# Sheet2.net
KiCad netlist of a schematic drawn in Altium Designer
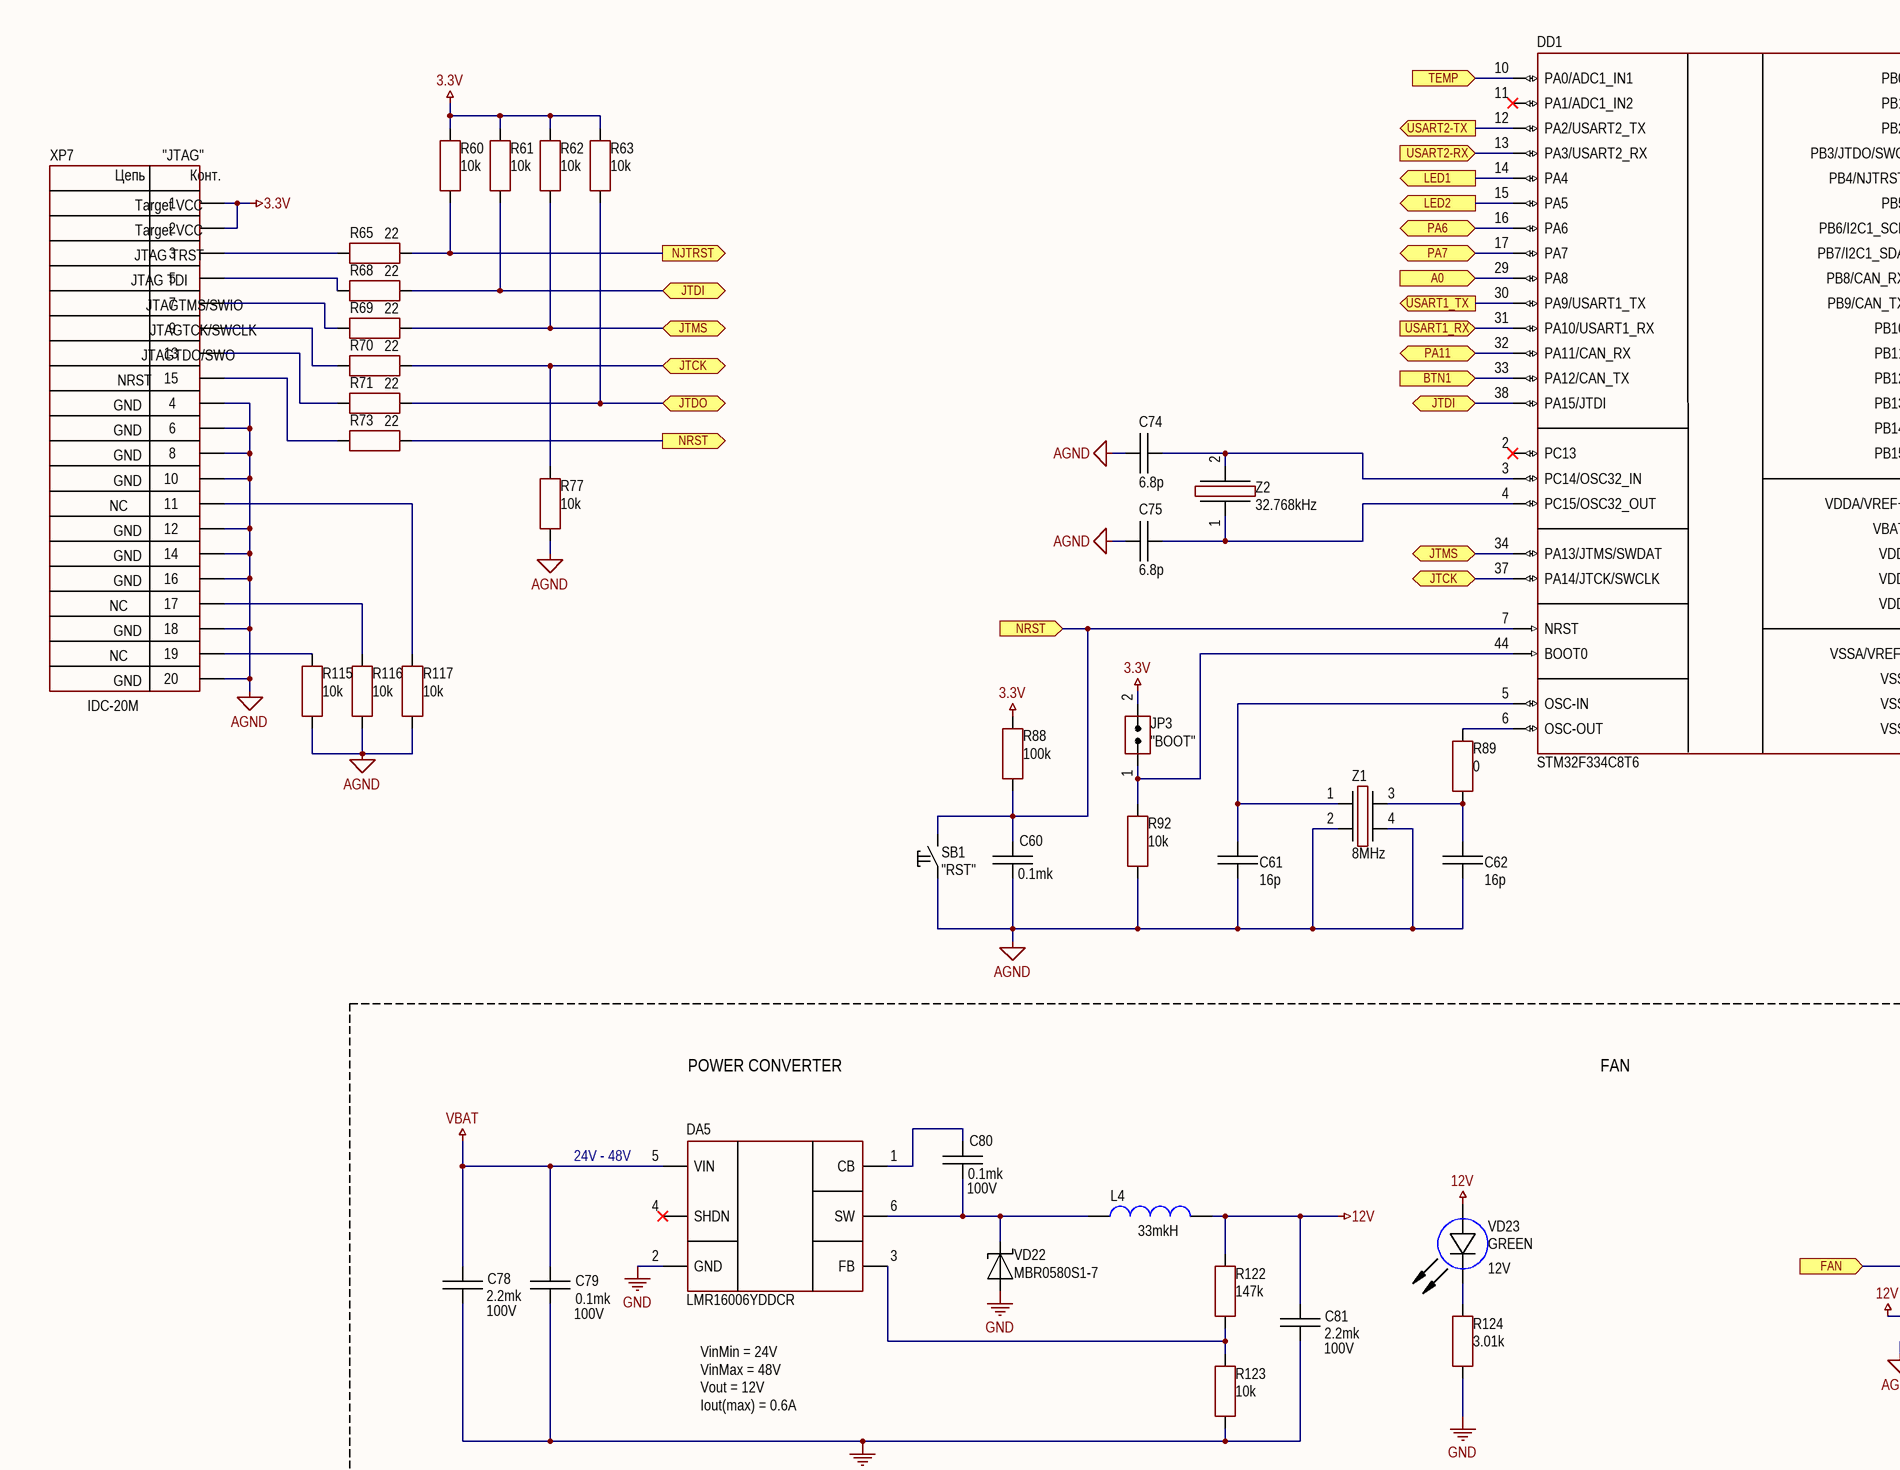
[diagram p0: Sheet2.SchDoc, top left]
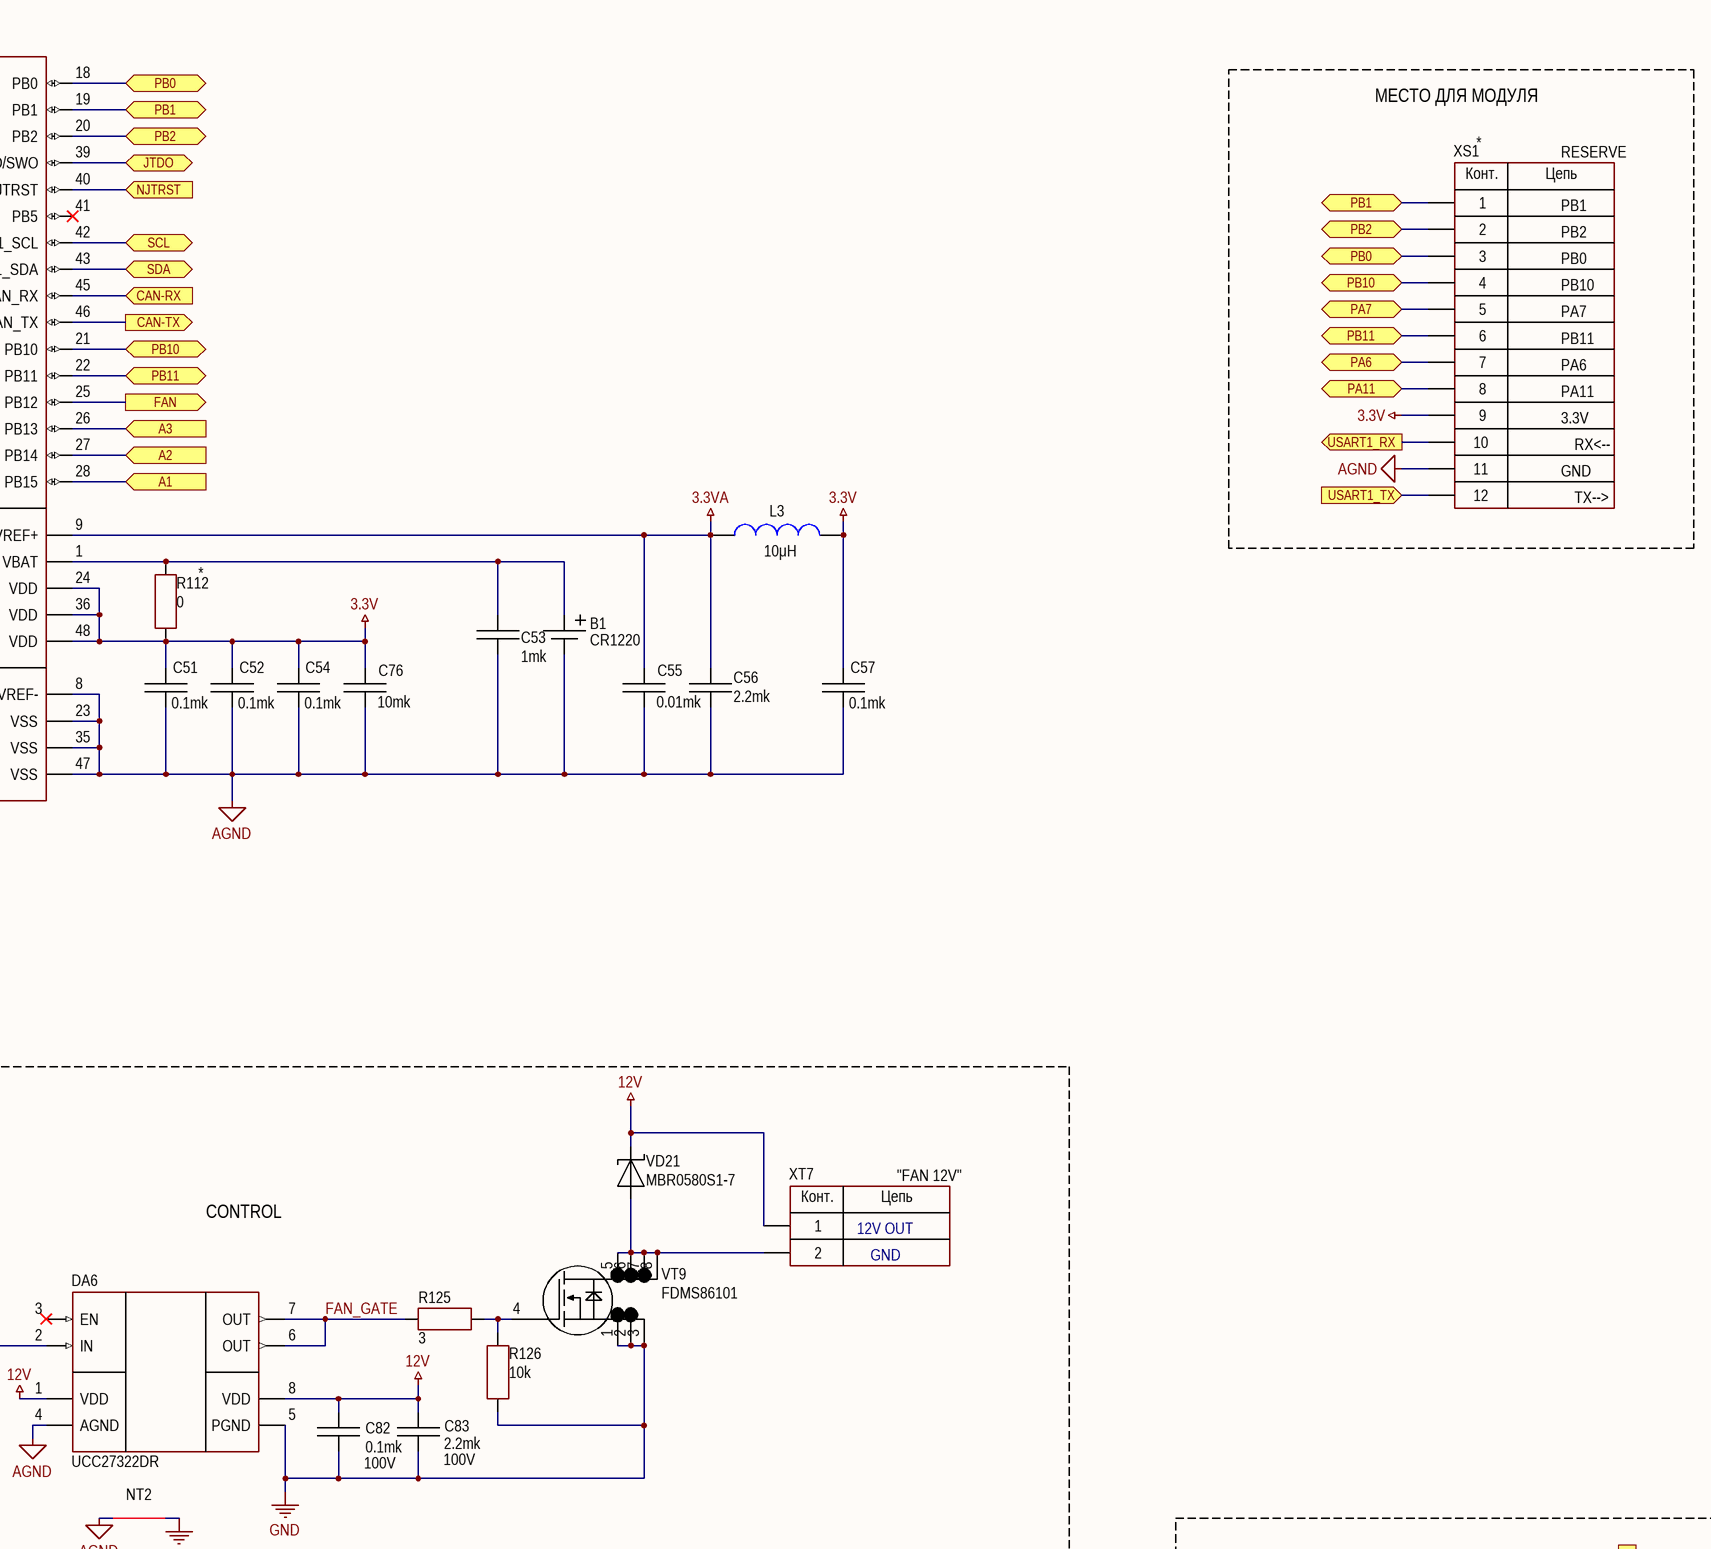
[diagram p1: Sheet2.SchDoc, top right]
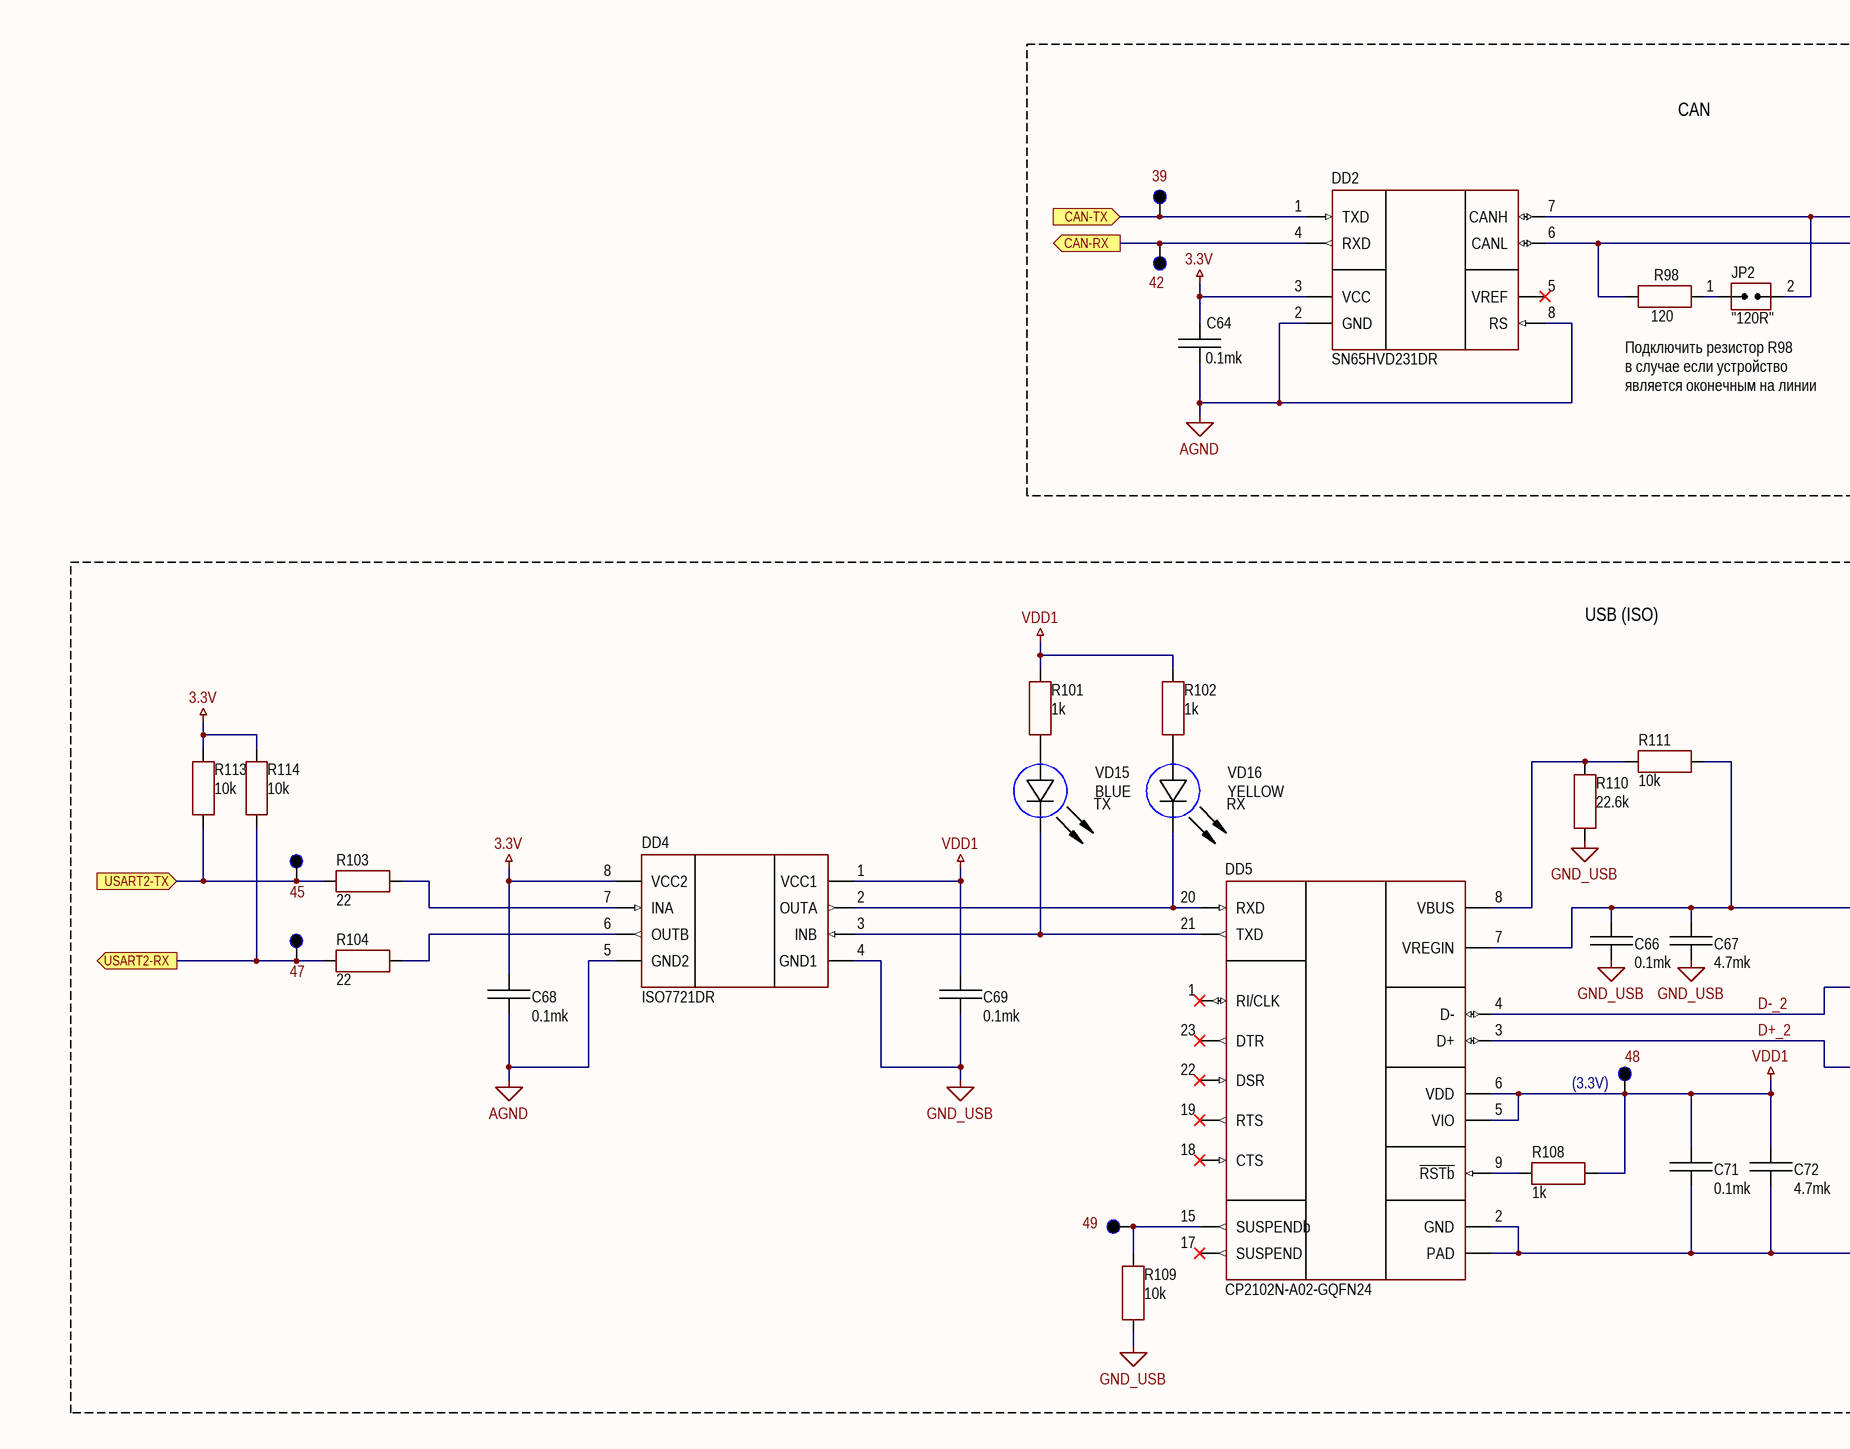
[diagram p2: Sheet2.SchDoc, bottom left]
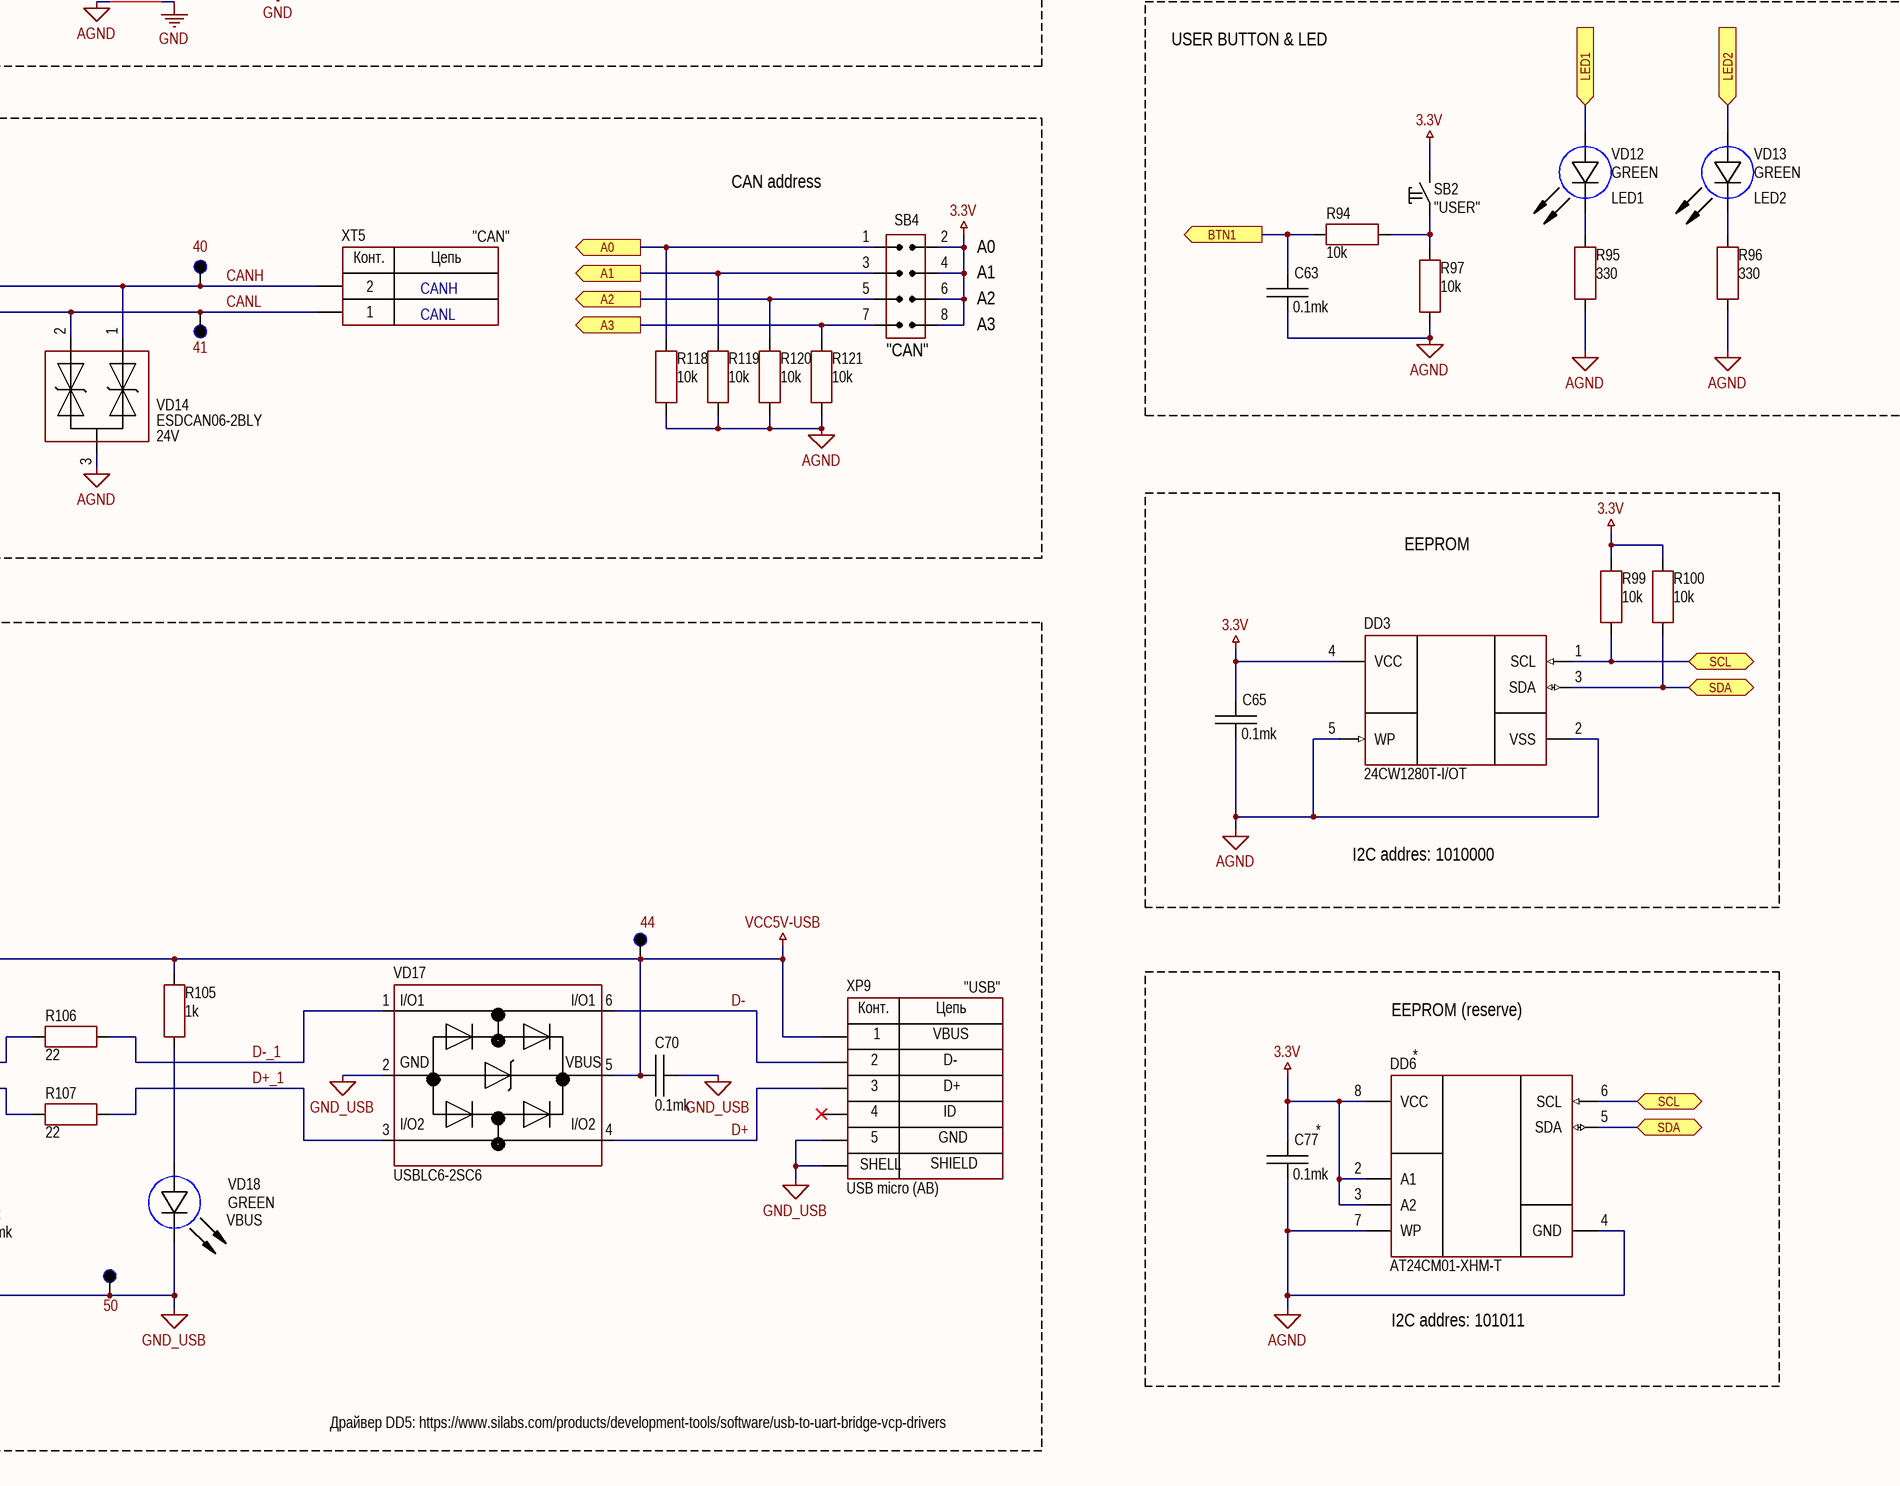
[diagram p3: Sheet2.SchDoc, bottom right]

(export (version "E")
  (design (tool "Eeschema 10.0.6"))
  (components
    (comp (ref "39")
      (value "test")
      (footprint "TEST_point_SMD")
      (description "Контактная площадка без компонента")
      (libsource (lib "Connector") (part "TEST point"))
    )
    (comp (ref "40")
      (value "test")
      (footprint "TEST_point_SMD")
      (description "Контактная площадка без компонента")
      (libsource (lib "Connector") (part "TEST point"))
    )
    (comp (ref "41")
      (value "test")
      (footprint "TEST_point_SMD")
      (description "Контактная площадка без компонента")
      (libsource (lib "Connector") (part "TEST point"))
    )
    (comp (ref "42")
      (value "test")
      (footprint "TEST_point_SMD")
      (description "Контактная площадка без компонента")
      (libsource (lib "Connector") (part "TEST point"))
    )
    (comp (ref "44")
      (value "test")
      (footprint "TEST_point_SMD")
      (description "Контактная площадка без компонента")
      (libsource (lib "Connector") (part "TEST point"))
    )
    (comp (ref "45")
      (value "test")
      (footprint "TEST_point_SMD")
      (description "Контактная площадка без компонента")
      (libsource (lib "Connector") (part "TEST point"))
    )
    (comp (ref "47")
      (value "test")
      (footprint "TEST_point_SMD")
      (description "Контактная площадка без компонента")
      (libsource (lib "Connector") (part "TEST point"))
    )
    (comp (ref "48")
      (value "test")
      (footprint "TEST_point_SMD")
      (description "Контактная площадка без компонента")
      (libsource (lib "Connector") (part "TEST point"))
    )
    (comp (ref "49")
      (value "test")
      (footprint "TEST_point_SMD")
      (description "Контактная площадка без компонента")
      (libsource (lib "Connector") (part "TEST point"))
    )
    (comp (ref "50")
      (value "test")
      (footprint "TEST_point_SMD")
      (description "Контактная площадка без компонента")
      (libsource (lib "Connector") (part "TEST point"))
    )
    (comp (ref "B1")
      (value "CR1220")
      (footprint "BAT: S8411-45R")
      (libsource (lib "Electromechanics") (part "CR1220"))
    )
    (comp (ref "C51")
      (value "0.1mk")
      (footprint "PCB_MPPT:CAP: 0603")
      (fields
        (field (name "MANUFACTURER") "AVX")
        (field (name "PARTNUMBER") "0603YC104KAT2A")
        (field (name "VALUEMANUFACTURERPARTNUMBER") "CAP CER, 0.1mk, X7R, ±10%, 16V, 0603")
      )
      (libsource (lib "Capacitor") (part "Ceramic_0603"))
    )
    (comp (ref "C52")
      (value "0.1mk")
      (footprint "PCB_MPPT:CAP: 0603")
      (fields
        (field (name "MANUFACTURER") "AVX")
        (field (name "PARTNUMBER") "0603YC104KAT2A")
        (field (name "VALUEMANUFACTURERPARTNUMBER") "CAP CER, 0.1mk, X7R, ±10%, 16V, 0603")
      )
      (libsource (lib "Capacitor") (part "Ceramic_0603"))
    )
    (comp (ref "C53")
      (value "1mk")
      (footprint "PCB_MPPT:CAP: 0603")
      (fields
        (field (name "MANUFACTURER") "AVX")
        (field (name "PARTNUMBER") "0603YC105KAT2A")
        (field (name "VALUEMANUFACTURERPARTNUMBER") "CAP CER, 1mk, X7R, ±10%, 16V, 0603")
      )
      (libsource (lib "Capacitor") (part "Ceramic_0603"))
    )
    (comp (ref "C54")
      (value "0.1mk")
      (footprint "PCB_MPPT:CAP: 0603")
      (fields
        (field (name "MANUFACTURER") "AVX")
        (field (name "PARTNUMBER") "0603YC104KAT2A")
        (field (name "VALUEMANUFACTURERPARTNUMBER") "CAP CER, 0.1mk, X7R, ±10%, 16V, 0603")
      )
      (libsource (lib "Capacitor") (part "Ceramic_0603"))
    )
    (comp (ref "C55")
      (value "0.01mk")
      (footprint "PCB_MPPT:CAP: 0603")
      (fields
        (field (name "MANUFACTURER") "AVX")
        (field (name "PARTNUMBER") "06031C103KAT2A")
        (field (name "VALUEMANUFACTURERPARTNUMBER") "CAP CER, 0.01mk, X7R, ±10%, 100V, 0603")
      )
      (libsource (lib "Capacitor") (part "Ceramic_0603"))
    )
    (comp (ref "C56")
      (value "2.2mk")
      (footprint "PCB_MPPT:CAP: 0603")
      (fields
        (field (name "MANUFACTURER") "AVX")
        (field (name "PARTNUMBER") "0603ZD225KAT2A")
        (field (name "VALUEMANUFACTURERPARTNUMBER") "CAP CER, 2.2mk, X5R, ±10%, 10V, 0603")
      )
      (libsource (lib "Capacitor") (part "Ceramic_0603"))
    )
    (comp (ref "C57")
      (value "0.1mk")
      (footprint "PCB_MPPT:CAP: 0603")
      (fields
        (field (name "MANUFACTURER") "AVX")
        (field (name "PARTNUMBER") "0603YC104KAT2A")
        (field (name "VALUEMANUFACTURERPARTNUMBER") "CAP CER, 0.1mk, X7R, ±10%, 16V, 0603")
      )
      (libsource (lib "Capacitor") (part "Ceramic_0603"))
    )
    (comp (ref "C60")
      (value "0.1mk")
      (footprint "PCB_MPPT:CAP: 0603")
      (fields
        (field (name "MANUFACTURER") "AVX")
        (field (name "PARTNUMBER") "0603YC104KAT2A")
        (field (name "VALUEMANUFACTURERPARTNUMBER") "CAP CER, 0.1mk, X7R, ±10%, 16V, 0603")
      )
      (libsource (lib "Capacitor") (part "Ceramic_0603"))
    )
    (comp (ref "C61")
      (value "16p")
      (footprint "PCB_MPPT:CAP: 0603")
      (fields
        (field (name "MANUFACTURER") "AVX")
        (field (name "PARTNUMBER") "06035A160JAT2A")
        (field (name "VALUEMANUFACTURERPARTNUMBER") "CAP CER, 16p, NP0, ±5%, 50V, 0603")
      )
      (libsource (lib "Capacitor") (part "Ceramic_0603"))
    )
    (comp (ref "C62")
      (value "16p")
      (footprint "PCB_MPPT:CAP: 0603")
      (fields
        (field (name "MANUFACTURER") "AVX")
        (field (name "PARTNUMBER") "06035A160JAT2A")
        (field (name "VALUEMANUFACTURERPARTNUMBER") "CAP CER, 16p, NP0, ±5%, 50V, 0603")
      )
      (libsource (lib "Capacitor") (part "Ceramic_0603"))
    )
    (comp (ref "C63")
      (value "0.1mk")
      (footprint "PCB_MPPT:CAP: 0603")
      (fields
        (field (name "MANUFACTURER") "AVX")
        (field (name "PARTNUMBER") "0603YC104KAT2A")
        (field (name "VALUEMANUFACTURERPARTNUMBER") "CAP CER, 0.1mk, X7R, ±10%, 16V, 0603")
      )
      (libsource (lib "Capacitor") (part "Ceramic_0603"))
    )
    (comp (ref "C64")
      (value "0.1mk")
      (footprint "PCB_MPPT:CAP: 0603")
      (fields
        (field (name "MANUFACTURER") "AVX")
        (field (name "PARTNUMBER") "0603YC104KAT2A")
        (field (name "VALUEMANUFACTURERPARTNUMBER") "CAP CER, 0.1mk, X7R, ±10%, 16V, 0603")
      )
      (libsource (lib "Capacitor") (part "Ceramic_0603"))
    )
    (comp (ref "C65")
      (value "0.1mk")
      (footprint "PCB_MPPT:CAP: 0603")
      (fields
        (field (name "MANUFACTURER") "AVX")
        (field (name "PARTNUMBER") "0603YC104KAT2A")
        (field (name "VALUEMANUFACTURERPARTNUMBER") "CAP CER, 0.1mk, X7R, ±10%, 16V, 0603")
      )
      (libsource (lib "Capacitor") (part "Ceramic_0603"))
    )
    (comp (ref "C66")
      (value "0.1mk")
      (footprint "PCB_MPPT:CAP: 0603")
      (fields
        (field (name "MANUFACTURER") "AVX")
        (field (name "PARTNUMBER") "0603YC104KAT2A")
        (field (name "VALUEMANUFACTURERPARTNUMBER") "CAP CER, 0.1mk, X7R, ±10%, 16V, 0603")
      )
      (libsource (lib "Capacitor") (part "Ceramic_0603"))
    )
    (comp (ref "C67")
      (value "4.7mk")
      (footprint "PCB_MPPT:CAP: 0805")
      (fields
        (field (name "MANUFACTURER") "AVX")
        (field (name "PARTNUMBER") "0805YC475KAT2A")
        (field (name "VALUEMANUFACTURERPARTNUMBER") "CAP CER, 4.7mk, X7R, ±10%, 16V, 0805")
      )
      (libsource (lib "Capacitor") (part "Ceramic_0805"))
    )
    (comp (ref "C68")
      (value "0.1mk")
      (footprint "PCB_MPPT:CAP: 0603")
      (fields
        (field (name "MANUFACTURER") "AVX")
        (field (name "PARTNUMBER") "0603YC104KAT2A")
        (field (name "VALUEMANUFACTURERPARTNUMBER") "CAP CER, 0.1mk, X7R, ±10%, 16V, 0603")
      )
      (libsource (lib "Capacitor") (part "Ceramic_0603"))
    )
    (comp (ref "C69")
      (value "0.1mk")
      (footprint "PCB_MPPT:CAP: 0603")
      (fields
        (field (name "MANUFACTURER") "AVX")
        (field (name "PARTNUMBER") "0603YC104KAT2A")
        (field (name "VALUEMANUFACTURERPARTNUMBER") "CAP CER, 0.1mk, X7R, ±10%, 16V, 0603")
      )
      (libsource (lib "Capacitor") (part "Ceramic_0603"))
    )
    (comp (ref "C70")
      (value "0.1mk")
      (footprint "PCB_MPPT:CAP: 0603")
      (fields
        (field (name "MANUFACTURER") "AVX")
        (field (name "PARTNUMBER") "0603YC104KAT2A")
        (field (name "VALUEMANUFACTURERPARTNUMBER") "CAP CER, 0.1mk, X7R, ±10%, 16V, 0603")
      )
      (libsource (lib "Capacitor") (part "Ceramic_0603"))
    )
    (comp (ref "C71")
      (value "0.1mk")
      (footprint "PCB_MPPT:CAP: 0603")
      (fields
        (field (name "MANUFACTURER") "AVX")
        (field (name "PARTNUMBER") "0603YC104KAT2A")
        (field (name "VALUEMANUFACTURERPARTNUMBER") "CAP CER, 0.1mk, X7R, ±10%, 16V, 0603")
      )
      (libsource (lib "Capacitor") (part "Ceramic_0603"))
    )
    (comp (ref "C72")
      (value "4.7mk")
      (footprint "PCB_MPPT:CAP: 0805")
      (fields
        (field (name "MANUFACTURER") "AVX")
        (field (name "PARTNUMBER") "0805YC475KAT2A")
        (field (name "VALUEMANUFACTURERPARTNUMBER") "CAP CER, 4.7mk, X7R, ±10%, 16V, 0805")
      )
      (libsource (lib "Capacitor") (part "Ceramic_0805"))
    )
    (comp (ref "C74")
      (value "6.8p")
      (footprint "PCB_MPPT:CAP: 0603")
      (fields
        (field (name "MANUFACTURER") "YAGEO")
        (field (name "PARTNUMBER") "CC0603DRNPO9BN6R8")
        (field (name "VALUEMANUFACTURERPARTNUMBER") "CAP CER, 6.8p, NP0, ±0.5pF, 50V, 0603")
      )
      (libsource (lib "Capacitor") (part "Ceramic_0603"))
    )
    (comp (ref "C75")
      (value "6.8p")
      (footprint "PCB_MPPT:CAP: 0603")
      (fields
        (field (name "MANUFACTURER") "YAGEO")
        (field (name "PARTNUMBER") "CC0603DRNPO9BN6R8")
        (field (name "VALUEMANUFACTURERPARTNUMBER") "CAP CER, 6.8p, NP0, ±0.5pF, 50V, 0603")
      )
      (libsource (lib "Capacitor") (part "Ceramic_0603"))
    )
    (comp (ref "C76")
      (value "10mk")
      (footprint "PCB_MPPT:CAP: 0603")
      (fields
        (field (name "MANUFACTURER") "AVX")
        (field (name "PARTNUMBER") "0603ZD106MAT2A")
        (field (name "VALUEMANUFACTURERPARTNUMBER") "CAP CER, 10mk, X5R, ±10%, 10V, 0603")
      )
      (libsource (lib "Capacitor") (part "Ceramic_0603"))
    )
    (comp (ref "C77")
      (value "0.1mk")
      (footprint "PCB_MPPT:CAP: 0603")
      (fields
        (field (name "MANUFACTURER") "AVX")
        (field (name "PARTNUMBER") "0603YC104KAT2A")
        (field (name "VALUEMANUFACTURERPARTNUMBER") "CAP CER, 0.1mk, X7R, ±10%, 16V, 0603")
      )
      (libsource (lib "Capacitor") (part "Ceramic_0603"))
    )
    (comp (ref "C78")
      (value "2.2mk")
      (footprint "PCB_MPPT:CAP: 1210")
      (fields
        (field (name "MANUFACTURER") "AVX")
        (field (name "PARTNUMBER") "12101C225KAT2A")
        (field (name "VALUEMANUFACTURERPARTNUMBER") "CAP CER, 2.2mk, X7R, ±10%, 100V, 1210")
        (field (name "VOLTAGE") "100V")
      )
      (libsource (lib "Capacitor") (part "Ceramic_1210"))
    )
    (comp (ref "C79")
      (value "0.1mk")
      (footprint "PCB_MPPT:CAP: 0603")
      (fields
        (field (name "MANUFACTURER") "AVX")
        (field (name "PARTNUMBER") "06031C104KAT2A")
        (field (name "VALUEMANUFACTURERPARTNUMBER") "CAP CER, 0.1mk, X7R, ±10%, 100V, 0603")
        (field (name "VOLTAGE") "100V")
      )
      (libsource (lib "Capacitor") (part "Ceramic_0603"))
    )
    (comp (ref "C80")
      (value "0.1mk")
      (footprint "PCB_MPPT:CAP: 0603")
      (fields
        (field (name "MANUFACTURER") "AVX")
        (field (name "PARTNUMBER") "06031C104KAT2A")
        (field (name "VALUEMANUFACTURERPARTNUMBER") "CAP CER, 0.1mk, X7R, ±10%, 100V, 0603")
        (field (name "VOLTAGE") "100V")
      )
      (libsource (lib "Capacitor") (part "Ceramic_0603"))
    )
    (comp (ref "C81")
      (value "2.2mk")
      (footprint "PCB_MPPT:CAP: 1210")
      (fields
        (field (name "MANUFACTURER") "AVX")
        (field (name "PARTNUMBER") "12101C225KAT2A")
        (field (name "VALUEMANUFACTURERPARTNUMBER") "CAP CER, 2.2mk, X7R, ±10%, 100V, 1210")
        (field (name "VOLTAGE") "100V")
      )
      (libsource (lib "Capacitor") (part "Ceramic_1210"))
    )
    (comp (ref "C82")
      (value "0.1mk")
      (footprint "PCB_MPPT:CAP: 0603")
      (fields
        (field (name "MANUFACTURER") "AVX")
        (field (name "PARTNUMBER") "06031C104KAT2A")
        (field (name "VALUEMANUFACTURERPARTNUMBER") "CAP CER, 0.1mk, X7R, ±10%, 100V, 0603")
        (field (name "VOLTAGE") "100V")
      )
      (libsource (lib "Capacitor") (part "Ceramic_0603"))
    )
    (comp (ref "C83")
      (value "2.2mk")
      (footprint "PCB_MPPT:CAP: 1210")
      (fields
        (field (name "MANUFACTURER") "AVX")
        (field (name "PARTNUMBER") "12101C225KAT2A")
        (field (name "VALUEMANUFACTURERPARTNUMBER") "CAP CER, 2.2mk, X7R, ±10%, 100V, 1210")
        (field (name "VOLTAGE") "100V")
      )
      (libsource (lib "Capacitor") (part "Ceramic_1210"))
    )
    (comp (ref "DA5")
      (value "~")
      (footprint "StandardCase:SOT23-6 Thin")
      (description "Buck converter")
      (fields
        (field (name "MANUFACTURER") "Texas Instruments")
        (field (name "VALUEMANUFACTURERPARTNUMBER") "DC/DC buck converter, SOT23-6")
        (field (name "PARTNUMBER") "LMR16006YDDCR")
      )
      (libsource (lib "IC. Power supply") (part "LMR16006YDDCR"))
    )
    (comp (ref "DA6")
      (value "~")
      (footprint "StandardCase:8-SOIC")
      (description "Gate driver")
      (fields
        (field (name "MANUFACTURER") "Texas Instruments")
        (field (name "VALUEMANUFACTURERPARTNUMBER") "Low side gate driver, P+N channel, 500kHz, ±9A, supply 4...15V, -40...+125°C, 8-SOIC")
        (field (name "PARTNUMBER") "UCC27322DR")
      )
      (libsource (lib "IC. Gate driver") (part "UCC27322D"))
    )
    (comp (ref "DD1")
      (value "IC microcontroller, 32-Bit, Cortex-M4, 72MHz, 64KB, 12KB, 48-LQFP")
      (footprint "PCB_MPPT:48-LQFP")
      (description "Cortex-M4")
      (fields (field (name "MANUFACTURER") "STMicroelectronics") (field (name "PARTNUMBER") "STM32F334C8T6"))
      (libsource (lib "IC. MCU") (part "STM32F334C4T6"))
    )
    (comp (ref "DD2")
      (value "~")
      (footprint "PCB_MPPT:8-SOIC")
      (description "CAN")
      (fields
        (field (name "MANUFACTURER") "Texas Instruments")
        (field (name "VALUEMANUFACTURERPARTNUMBER") "IC CAN transceiver, 8-SOIC")
        (field (name "PARTNUMBER") "SN65HVD231DR")
      )
      (libsource (lib "IC. Interface") (part "SN65HVD231DR"))
    )
    (comp (ref "DD3")
      (value "~")
      (footprint "PCB_MPPT:SOT23-5")
      (description "EEPROM")
      (fields
        (field (name "MANUFACTURER") "Microchip Technology")
        (field (name "VALUEMANUFACTURERPARTNUMBER") "EEPROM, 128KB (16Kx8), 400 kHz, I2C, SOT-23-5")
        (field (name "PARTNUMBER") "24CW1280T-I/OT")
      )
      (libsource (lib "IC. Memory") (part "24AA01T"))
    )
    (comp (ref "DD4")
      (value "~")
      (footprint "PCB_MPPT:8-SOIC")
      (description "Digital isolator")
      (fields
        (field (name "MANUFACTURER") "Texas Instruments")
        (field (name "VALUEMANUFACTURERPARTNUMBER") "IC digital isolator, 8-SOIC")
        (field (name "PARTNUMBER") "ISO7721DR")
      )
      (libsource (lib "IC. Interface") (part "ISO7721DR"))
    )
    (comp (ref "DD5")
      (value "~")
      (footprint "PCB_MPPT:24-QFN")
      (description "USB-to-UART")
      (fields
        (field (name "MANUFACTURER") "Silicon Labs")
        (field (name "VALUEMANUFACTURERPARTNUMBER") "USB Bridge, USB to UART, USB2.0, 24-QFN(4x4)")
        (field (name "PARTNUMBER") "CP2102N-A02-GQFN24")
      )
      (libsource (lib "IC. Interface") (part "CP2102N_QFN24"))
    )
    (comp (ref "DD6")
      (value "EEPROM Memory IC 1Mb (128K x 8) I²C 1MHz 550ns 8-TSSOP")
      (footprint "8-TSSOP")
      (description "EEPROM")
      (fields
        (field (name "MANUFACTURER") "Microchip Technology")
        (field (name "PARTNUMBER") "AT24CM01-XHM-T")
      )
      (libsource (lib "IC. Memory") (part "AT24CM01-XHM-T"))
    )
    (comp (ref "JP2")
      (value "~")
      (footprint "PCB_MPPT:CON: PLS-2")
      (fields
        (field (name "COMMENTTEXT") "\"120R\"")
        (field (name "MANUFACTURER") "Würth Elektronik")
        (field (name "PARTNUMBER") "61300411121")
        (field (name "VALUEMANUFACTURERPARTNUMBER") "PLS-2 SINGLE ROW, 2pin, 2.54mm, 500VAC, 3A")
      )
      (libsource (lib "") (part "Jumper_single_1"))
    )
    (comp (ref "JP3")
      (value "~")
      (footprint "PCB_MPPT:CON: PLS-2")
      (fields
        (field (name "COMMENTTEXT") "\"BOOT\"")
        (field (name "MANUFACTURER") "Würth Elektronik")
        (field (name "PARTNUMBER") "61300411121")
        (field (name "VALUEMANUFACTURERPARTNUMBER") "PLS-2 SINGLE ROW, 2pin, 2.54mm, 500VAC, 3A")
      )
      (libsource (lib "Connector") (part "Jumper_single"))
    )
    (comp (ref "L3")
      (value "10μH")
      (footprint "PCB_MPPT:IND: 0805")
      (fields
        (field (name "MANUFACTURER") "Murata Electronics")
        (field (name "PARTNUMBER") "LQM21DH100M70L")
        (field (name "VALUEMANUFACTURERPARTNUMBER") "Fixed inductor, 10μH, ±20%, 0805, 250mA")
      )
      (libsource (lib "Inductor") (part "Inductor_0805"))
    )
    (comp (ref "L4")
      (value "33mkH")
      (footprint "PCB_MPPT:IND: SRU8043")
      (fields
        (field (name "MANUFACTURER") "Bourns Inc.")
        (field (name "PARTNUMBER") "SRU8043-330Y")
        (field (name "VALUEMANUFACTURERPARTNUMBER") "Fixed inductor, 33mkH, ±15%, SMD Nonstandard, Ferrite, , 1.7A")
      )
      (libsource (lib "Inductor") (part "Inductor_R22.9/14/7.62"))
    )
    (comp (ref "NT2")
      (value "~")
      (footprint "PCB_MPPT:NET_TIE")
      (libsource (lib "Connector") (part "NetTie"))
    )
    (comp (ref "R60")
      (value "10k")
      (footprint "PCB_MPPT:RES: 0603")
      (fields
        (field (name "MANUFACTURER") "Vishay")
        (field (name "PARTNUMBER") "CRCW060310K0JNEAC")
        (field (name "VALUEMANUFACTURERPARTNUMBER") "Res, SMD, 10k, ±5%, 0603, 0.1W")
      )
      (libsource (lib "Resistor") (part "Resistor_0603"))
    )
    (comp (ref "R61")
      (value "10k")
      (footprint "PCB_MPPT:RES: 0603")
      (fields
        (field (name "MANUFACTURER") "Vishay")
        (field (name "PARTNUMBER") "CRCW060310K0JNEAC")
        (field (name "VALUEMANUFACTURERPARTNUMBER") "Res, SMD, 10k, ±5%, 0603, 0.1W")
      )
      (libsource (lib "Resistor") (part "Resistor_0603"))
    )
    (comp (ref "R62")
      (value "10k")
      (footprint "PCB_MPPT:RES: 0603")
      (fields
        (field (name "MANUFACTURER") "Vishay")
        (field (name "PARTNUMBER") "CRCW060310K0JNEAC")
        (field (name "VALUEMANUFACTURERPARTNUMBER") "Res, SMD, 10k, ±5%, 0603, 0.1W")
      )
      (libsource (lib "Resistor") (part "Resistor_0603"))
    )
    (comp (ref "R63")
      (value "10k")
      (footprint "PCB_MPPT:RES: 0603")
      (fields
        (field (name "MANUFACTURER") "Vishay")
        (field (name "PARTNUMBER") "CRCW060310K0JNEAC")
        (field (name "VALUEMANUFACTURERPARTNUMBER") "Res, SMD, 10k, ±5%, 0603, 0.1W")
      )
      (libsource (lib "Resistor") (part "Resistor_0603"))
    )
    (comp (ref "R65")
      (value "22")
      (footprint "PCB_MPPT:RES: 0603")
      (fields
        (field (name "MANUFACTURER") "Vishay")
        (field (name "PARTNUMBER") "CRCW060322R0JNEA")
        (field (name "VALUEMANUFACTURERPARTNUMBER") "Res, SMD, 22, ±5%, 0603, 0.1W")
      )
      (libsource (lib "") (part "Resistor_0603_1"))
    )
    (comp (ref "R68")
      (value "22")
      (footprint "PCB_MPPT:RES: 0603")
      (fields
        (field (name "MANUFACTURER") "Vishay")
        (field (name "PARTNUMBER") "CRCW060322R0JNEA")
        (field (name "VALUEMANUFACTURERPARTNUMBER") "Res, SMD, 22, ±5%, 0603, 0.1W")
      )
      (libsource (lib "") (part "Resistor_0603_1"))
    )
    (comp (ref "R69")
      (value "22")
      (footprint "PCB_MPPT:RES: 0603")
      (fields
        (field (name "MANUFACTURER") "Vishay")
        (field (name "PARTNUMBER") "CRCW060322R0JNEA")
        (field (name "VALUEMANUFACTURERPARTNUMBER") "Res, SMD, 22, ±5%, 0603, 0.1W")
      )
      (libsource (lib "") (part "Resistor_0603_1"))
    )
    (comp (ref "R70")
      (value "22")
      (footprint "PCB_MPPT:RES: 0603")
      (fields
        (field (name "MANUFACTURER") "Vishay")
        (field (name "PARTNUMBER") "CRCW060322R0JNEA")
        (field (name "VALUEMANUFACTURERPARTNUMBER") "Res, SMD, 22, ±5%, 0603, 0.1W")
      )
      (libsource (lib "") (part "Resistor_0603_1"))
    )
    (comp (ref "R71")
      (value "22")
      (footprint "PCB_MPPT:RES: 0603")
      (fields
        (field (name "MANUFACTURER") "Vishay")
        (field (name "PARTNUMBER") "CRCW060322R0JNEA")
        (field (name "VALUEMANUFACTURERPARTNUMBER") "Res, SMD, 22, ±5%, 0603, 0.1W")
      )
      (libsource (lib "") (part "Resistor_0603_1"))
    )
    (comp (ref "R73")
      (value "22")
      (footprint "PCB_MPPT:RES: 0603")
      (fields
        (field (name "MANUFACTURER") "Vishay")
        (field (name "PARTNUMBER") "CRCW060322R0JNEA")
        (field (name "VALUEMANUFACTURERPARTNUMBER") "Res, SMD, 22, ±5%, 0603, 0.1W")
      )
      (libsource (lib "") (part "Resistor_0603_1"))
    )
    (comp (ref "R77")
      (value "10k")
      (footprint "PCB_MPPT:RES: 0603")
      (fields
        (field (name "MANUFACTURER") "Vishay")
        (field (name "PARTNUMBER") "CRCW060310K0JNEAC")
        (field (name "VALUEMANUFACTURERPARTNUMBER") "Res, SMD, 10k, ±5%, 0603, 0.1W")
      )
      (libsource (lib "Resistor") (part "Resistor_0603"))
    )
    (comp (ref "R88")
      (value "100k")
      (footprint "PCB_MPPT:RES: 0603")
      (fields
        (field (name "MANUFACTURER") "Vishay")
        (field (name "PARTNUMBER") "CRCW0603100KFKEA")
        (field (name "VALUEMANUFACTURERPARTNUMBER") "Res, SMD, 100k, ±1%, 0603, 0.1W")
      )
      (libsource (lib "Resistor") (part "Resistor_0603"))
    )
    (comp (ref "R89")
      (value "0")
      (footprint "PCB_MPPT:RES: 0603")
      (fields
        (field (name "MANUFACTURER") "Vishay")
        (field (name "PARTNUMBER") "CRCW06030000Z0EA")
        (field (name "VALUEMANUFACTURERPARTNUMBER") "Res, SMD, 0, ±1%, 0603, 0.1W")
      )
      (libsource (lib "") (part "Resistor_0603_2"))
    )
    (comp (ref "R92")
      (value "10k")
      (footprint "PCB_MPPT:RES: 0603")
      (fields
        (field (name "MANUFACTURER") "Vishay")
        (field (name "PARTNUMBER") "CRCW060310K0JNEAC")
        (field (name "VALUEMANUFACTURERPARTNUMBER") "Res, SMD, 10k, ±5%, 0603, 0.1W")
      )
      (libsource (lib "Resistor") (part "Resistor_0603"))
    )
    (comp (ref "R94")
      (value "10k")
      (footprint "PCB_MPPT:RES: 0603")
      (fields
        (field (name "MANUFACTURER") "Vishay")
        (field (name "PARTNUMBER") "CRCW060310K0JNEAC")
        (field (name "VALUEMANUFACTURERPARTNUMBER") "Res, SMD, 10k, ±5%, 0603, 0.1W")
      )
      (libsource (lib "") (part "Resistor_0603_1"))
    )
    (comp (ref "R95")
      (value "330")
      (footprint "PCB_MPPT:RES: 0603")
      (fields
        (field (name "MANUFACTURER") "Vishay")
        (field (name "PARTNUMBER") "CRCW0603330RFKEAC")
        (field (name "VALUEMANUFACTURERPARTNUMBER") "Res, SMD, 330, ±1%, 0603, 0.1W")
      )
      (libsource (lib "Resistor") (part "Resistor_0603"))
    )
    (comp (ref "R96")
      (value "330")
      (footprint "PCB_MPPT:RES: 0603")
      (fields
        (field (name "MANUFACTURER") "Vishay")
        (field (name "PARTNUMBER") "CRCW0603330RFKEAC")
        (field (name "VALUEMANUFACTURERPARTNUMBER") "Res, SMD, 330, ±1%, 0603, 0.1W")
      )
      (libsource (lib "Resistor") (part "Resistor_0603"))
    )
    (comp (ref "R97")
      (value "10k")
      (footprint "PCB_MPPT:RES: 0603")
      (fields
        (field (name "MANUFACTURER") "Vishay")
        (field (name "PARTNUMBER") "CRCW060310K0JNEAC")
        (field (name "VALUEMANUFACTURERPARTNUMBER") "Res, SMD, 10k, ±5%, 0603, 0.1W")
      )
      (libsource (lib "Resistor") (part "Resistor_0603"))
    )
    (comp (ref "R98")
      (value "120")
      (footprint "PCB_MPPT:RES: 0805")
      (fields
        (field (name "MANUFACTURER") "Vishay")
        (field (name "PARTNUMBER") "CRCW0805120RJNEA")
        (field (name "VALUEMANUFACTURERPARTNUMBER") "Resistor film, 120, ±5%, 0805, 0.125W")
      )
      (libsource (lib "Resistor") (part "Resistor_0805"))
    )
    (comp (ref "R99")
      (value "10k")
      (footprint "PCB_MPPT:RES: 0603")
      (fields
        (field (name "MANUFACTURER") "Vishay")
        (field (name "PARTNUMBER") "CRCW060310K0JNEAC")
        (field (name "VALUEMANUFACTURERPARTNUMBER") "Res, SMD, 10k, ±5%, 0603, 0.1W")
      )
      (libsource (lib "") (part "Resistor_0603_2"))
    )
    (comp (ref "R100")
      (value "10k")
      (footprint "PCB_MPPT:RES: 0603")
      (fields
        (field (name "MANUFACTURER") "Vishay")
        (field (name "PARTNUMBER") "CRCW060310K0JNEAC")
        (field (name "VALUEMANUFACTURERPARTNUMBER") "Res, SMD, 10k, ±5%, 0603, 0.1W")
      )
      (libsource (lib "") (part "Resistor_0603_2"))
    )
    (comp (ref "R101")
      (value "1k")
      (footprint "PCB_MPPT:RES: 0603")
      (fields
        (field (name "MANUFACTURER") "Vishay")
        (field (name "PARTNUMBER") "CRCW06031K00FKEA")
        (field (name "VALUEMANUFACTURERPARTNUMBER") "Res, SMD, 1k, ±1%, 0603, 0.1W")
      )
      (libsource (lib "") (part "Resistor_0603_1"))
    )
    (comp (ref "R102")
      (value "1k")
      (footprint "PCB_MPPT:RES: 0603")
      (fields
        (field (name "MANUFACTURER") "Vishay")
        (field (name "PARTNUMBER") "CRCW06031K00FKEA")
        (field (name "VALUEMANUFACTURERPARTNUMBER") "Res, SMD, 1k, ±1%, 0603, 0.1W")
      )
      (libsource (lib "") (part "Resistor_0603_1"))
    )
    (comp (ref "R103")
      (value "22")
      (footprint "PCB_MPPT:RES: 0603")
      (fields
        (field (name "MANUFACTURER") "Vishay")
        (field (name "PARTNUMBER") "CRCW060322R0JNEA")
        (field (name "VALUEMANUFACTURERPARTNUMBER") "Res, SMD, 22, ±5%, 0603, 0.1W")
      )
      (libsource (lib "Resistor") (part "Resistor_0603"))
    )
    (comp (ref "R104")
      (value "22")
      (footprint "PCB_MPPT:RES: 0603")
      (fields
        (field (name "MANUFACTURER") "Vishay")
        (field (name "PARTNUMBER") "CRCW060322R0JNEA")
        (field (name "VALUEMANUFACTURERPARTNUMBER") "Res, SMD, 22, ±5%, 0603, 0.1W")
      )
      (libsource (lib "Resistor") (part "Resistor_0603"))
    )
    (comp (ref "R105")
      (value "1k")
      (footprint "PCB_MPPT:RES: 0603")
      (fields
        (field (name "MANUFACTURER") "Vishay")
        (field (name "PARTNUMBER") "CRCW06031K00FKEA")
        (field (name "VALUEMANUFACTURERPARTNUMBER") "Res, SMD, 1k, ±1%, 0603, 0.1W")
      )
      (libsource (lib "") (part "Resistor_0603_1"))
    )
    (comp (ref "R106")
      (value "22")
      (footprint "PCB_MPPT:RES: 0603")
      (fields
        (field (name "MANUFACTURER") "Vishay")
        (field (name "PARTNUMBER") "CRCW060322R0JNEA")
        (field (name "VALUEMANUFACTURERPARTNUMBER") "Res, SMD, 22, ±5%, 0603, 0.1W")
      )
      (libsource (lib "Resistor") (part "Resistor_0603"))
    )
    (comp (ref "R107")
      (value "22")
      (footprint "PCB_MPPT:RES: 0603")
      (fields
        (field (name "MANUFACTURER") "Vishay")
        (field (name "PARTNUMBER") "CRCW060322R0JNEA")
        (field (name "VALUEMANUFACTURERPARTNUMBER") "Res, SMD, 22, ±5%, 0603, 0.1W")
      )
      (libsource (lib "Resistor") (part "Resistor_0603"))
    )
    (comp (ref "R108")
      (value "1k")
      (footprint "PCB_MPPT:RES: 0603")
      (fields
        (field (name "MANUFACTURER") "Vishay")
        (field (name "PARTNUMBER") "CRCW06031K00FKEA")
        (field (name "VALUEMANUFACTURERPARTNUMBER") "Res, SMD, 1k, ±1%, 0603, 0.1W")
      )
      (libsource (lib "") (part "Resistor_0603_2"))
    )
    (comp (ref "R109")
      (value "10k")
      (footprint "PCB_MPPT:RES: 0603")
      (fields
        (field (name "MANUFACTURER") "Vishay")
        (field (name "PARTNUMBER") "CRCW060310K0JNEAC")
        (field (name "VALUEMANUFACTURERPARTNUMBER") "Res, SMD, 10k, ±5%, 0603, 0.1W")
      )
      (libsource (lib "Resistor") (part "Resistor_0603"))
    )
    (comp (ref "R110")
      (value "22.6k")
      (footprint "PCB_MPPT:RES: 0603")
      (fields
        (field (name "MANUFACTURER") "Vishay")
        (field (name "PARTNUMBER") "CRCW060322K6FKEA")
        (field (name "VALUEMANUFACTURERPARTNUMBER") "Res, SMD, 22.6k, ±1%, 0603, 0.1W")
      )
      (libsource (lib "") (part "Resistor_0603_2"))
    )
    (comp (ref "R111")
      (value "10k")
      (footprint "PCB_MPPT:RES: 0603")
      (fields
        (field (name "MANUFACTURER") "Vishay")
        (field (name "PARTNUMBER") "CRCW060310K0JNEAC")
        (field (name "VALUEMANUFACTURERPARTNUMBER") "Res, SMD, 10k, ±5%, 0603, 0.1W")
      )
      (libsource (lib "") (part "Resistor_0603_3"))
    )
    (comp (ref "R112")
      (value "0")
      (footprint "PCB_MPPT:RES: 0603")
      (fields
        (field (name "MANUFACTURER") "Vishay")
        (field (name "PARTNUMBER") "CRCW06030000Z0EA")
        (field (name "VALUEMANUFACTURERPARTNUMBER") "Res, SMD, 0, ±1%, 0603, 0.1W")
      )
      (libsource (lib "Resistor") (part "Resistor_0603"))
    )
    (comp (ref "R113")
      (value "10k")
      (footprint "PCB_MPPT:RES: 0603")
      (fields
        (field (name "MANUFACTURER") "Vishay")
        (field (name "PARTNUMBER") "CRCW060310K0JNEAC")
        (field (name "VALUEMANUFACTURERPARTNUMBER") "Res, SMD, 10k, ±5%, 0603, 0.1W")
      )
      (libsource (lib "Resistor") (part "Resistor_0603"))
    )
    (comp (ref "R114")
      (value "10k")
      (footprint "PCB_MPPT:RES: 0603")
      (fields
        (field (name "MANUFACTURER") "Vishay")
        (field (name "PARTNUMBER") "CRCW060310K0JNEAC")
        (field (name "VALUEMANUFACTURERPARTNUMBER") "Res, SMD, 10k, ±5%, 0603, 0.1W")
      )
      (libsource (lib "Resistor") (part "Resistor_0603"))
    )
    (comp (ref "R115")
      (value "10k")
      (footprint "PCB_MPPT:RES: 0603")
      (fields
        (field (name "MANUFACTURER") "Vishay")
        (field (name "PARTNUMBER") "CRCW060310K0JNEAC")
        (field (name "VALUEMANUFACTURERPARTNUMBER") "Res, SMD, 10k, ±5%, 0603, 0.1W")
      )
      (libsource (lib "Resistor") (part "Resistor_0603"))
    )
    (comp (ref "R116")
      (value "10k")
      (footprint "PCB_MPPT:RES: 0603")
      (fields
        (field (name "MANUFACTURER") "Vishay")
        (field (name "PARTNUMBER") "CRCW060310K0JNEAC")
        (field (name "VALUEMANUFACTURERPARTNUMBER") "Res, SMD, 10k, ±5%, 0603, 0.1W")
      )
      (libsource (lib "Resistor") (part "Resistor_0603"))
    )
    (comp (ref "R117")
      (value "10k")
      (footprint "PCB_MPPT:RES: 0603")
      (fields
        (field (name "MANUFACTURER") "Vishay")
        (field (name "PARTNUMBER") "CRCW060310K0JNEAC")
        (field (name "VALUEMANUFACTURERPARTNUMBER") "Res, SMD, 10k, ±5%, 0603, 0.1W")
      )
      (libsource (lib "Resistor") (part "Resistor_0603"))
    )
    (comp (ref "R118")
      (value "10k")
      (footprint "PCB_MPPT:RES: 0603")
      (fields
        (field (name "MANUFACTURER") "Vishay")
        (field (name "PARTNUMBER") "CRCW060310K0JNEAC")
        (field (name "VALUEMANUFACTURERPARTNUMBER") "Res, SMD, 10k, ±5%, 0603, 0.1W")
      )
      (libsource (lib "Resistor") (part "Resistor_0603"))
    )
    (comp (ref "R119")
      (value "10k")
      (footprint "PCB_MPPT:RES: 0603")
      (fields
        (field (name "MANUFACTURER") "Vishay")
        (field (name "PARTNUMBER") "CRCW060310K0JNEAC")
        (field (name "VALUEMANUFACTURERPARTNUMBER") "Res, SMD, 10k, ±5%, 0603, 0.1W")
      )
      (libsource (lib "Resistor") (part "Resistor_0603"))
    )
    (comp (ref "R120")
      (value "10k")
      (footprint "PCB_MPPT:RES: 0603")
      (fields
        (field (name "MANUFACTURER") "Vishay")
        (field (name "PARTNUMBER") "CRCW060310K0JNEAC")
        (field (name "VALUEMANUFACTURERPARTNUMBER") "Res, SMD, 10k, ±5%, 0603, 0.1W")
      )
      (libsource (lib "Resistor") (part "Resistor_0603"))
    )
    (comp (ref "R121")
      (value "10k")
      (footprint "PCB_MPPT:RES: 0603")
      (fields
        (field (name "MANUFACTURER") "Vishay")
        (field (name "PARTNUMBER") "CRCW060310K0JNEAC")
        (field (name "VALUEMANUFACTURERPARTNUMBER") "Res, SMD, 10k, ±5%, 0603, 0.1W")
      )
      (libsource (lib "Resistor") (part "Resistor_0603"))
    )
    (comp (ref "R122")
      (value "147k")
      (footprint "PCB_MPPT:RES: 0603")
      (fields
        (field (name "MANUFACTURER") "YAGEO")
        (field (name "PARTNUMBER") "RC0603FR-07147KL")
        (field (name "VALUEMANUFACTURERPARTNUMBER") "Res, SMD, 147k, ±1%, 0603, 0.1W")
      )
      (libsource (lib "Resistor") (part "Resistor_0603"))
    )
    (comp (ref "R123")
      (value "10k")
      (footprint "PCB_MPPT:RES: 0603")
      (fields
        (field (name "MANUFACTURER") "Vishay")
        (field (name "PARTNUMBER") "CRCW060310K0JNEAC")
        (field (name "VALUEMANUFACTURERPARTNUMBER") "Res, SMD, 10k, ±5%, 0603, 0.1W")
      )
      (libsource (lib "") (part "Resistor_0603_2"))
    )
    (comp (ref "R124")
      (value "3.01k")
      (footprint "PCB_MPPT:RES: 0603")
      (fields
        (field (name "MANUFACTURER") "Vishay")
        (field (name "PARTNUMBER") "CRCW06033K01FKEA")
        (field (name "VALUEMANUFACTURERPARTNUMBER") "Res, SMD, 3.01k, ±1%, 0603, 0.1W")
      )
      (libsource (lib "Resistor") (part "Resistor_0603"))
    )
    (comp (ref "R125")
      (value "3")
      (footprint "PCB_MPPT:RES: 0603")
      (fields
        (field (name "MANUFACTURER") "Vishay")
        (field (name "PARTNUMBER") "CRCW06033R00JNEA")
        (field (name "VALUEMANUFACTURERPARTNUMBER") "Res, SMD, 3, ±5%, 0603, 0.1W")
      )
      (libsource (lib "") (part "Resistor_0603_1"))
    )
    (comp (ref "R126")
      (value "10k")
      (footprint "PCB_MPPT:RES: 0603")
      (fields
        (field (name "MANUFACTURER") "Vishay")
        (field (name "PARTNUMBER") "CRCW060310K0JNEAC")
        (field (name "VALUEMANUFACTURERPARTNUMBER") "Res, SMD, 10k, ±5%, 0603, 0.1W")
      )
      (libsource (lib "") (part "Resistor_0603_2"))
    )
    (comp (ref "SB1")
      (value "~")
      (footprint "PCB_MPPT:BUT: 6x6 SMD")
      (fields
        (field (name "MANUFACTURER") "TE Connectivity")
        (field (name "VALUEMANUFACTURERPARTNUMBER") "Tactile button, 6x6mm")
        (field (name "PARTNUMBER") "FSM2JSMAATR")
        (field (name "COMMENTTEXT") "\"RST\"")
      )
      (libsource (lib "Electromechanics") (part "Button_tactile"))
    )
    (comp (ref "SB2")
      (value "~")
      (footprint "PCB_MPPT:BUT: 6x6 SMD")
      (fields
        (field (name "MANUFACTURER") "TE Connectivity")
        (field (name "VALUEMANUFACTURERPARTNUMBER") "Tactile button, 6x6mm")
        (field (name "PARTNUMBER") "FSM2JSMAATR")
        (field (name "COMMENTTEXT") "\"USER\"")
      )
      (libsource (lib "Electromechanics") (part "Button_tactile"))
    )
    (comp (ref "SB4")
      (value "~")
      (footprint "BUT; SW4_1571983_4P_T")
      (fields
        (field (name "MANUFACTURER") "TE Connectivity")
        (field (name "VALUEMANUFACTURERPARTNUMBER") "DIP switch, 4pin, 24VDC, 25mA, -40...+85°C")
        (field (name "PARTNUMBER") "1571983-4")
      )
      (libsource (lib "Electromechanics") (part "Button_switch"))
    )
    (comp (ref "VD12")
      (value "~")
      (footprint "PCB_MPPT:LED: 0603G")
      (fields
        (field (name "MANUFACTURER") "Wurth")
        (field (name "VALUEMANUFACTURERPARTNUMBER") "LED, 0603, GREEN")
        (field (name "PARTNUMBER") "150060VS75000")
        (field (name "COLOR") "GREEN")
        (field (name "SHOWCOMMENT") "LED1")
      )
      (libsource (lib "Diode") (part "LED_single"))
    )
    (comp (ref "VD13")
      (value "~")
      (footprint "PCB_MPPT:LED: 0603G")
      (fields
        (field (name "MANUFACTURER") "Wurth")
        (field (name "VALUEMANUFACTURERPARTNUMBER") "LED, 0603, GREEN")
        (field (name "PARTNUMBER") "150060VS75000")
        (field (name "COLOR") "GREEN")
        (field (name "SHOWCOMMENT") "LED2")
      )
      (libsource (lib "Diode") (part "LED_single"))
    )
    (comp (ref "VD14")
      (value "~")
      (footprint "PCB_MPPT:SOT23")
      (fields
        (field (name "MANUFACTURER") "STMicroelectronics")
        (field (name "VALUEMANUFACTURERPARTNUMBER") "TVS diode, 24V, 230W peak, 3A, 13pF, SOT-23, -40...+150°C")
        (field (name "VOLTAGE") "24V")
        (field (name "PARTNUMBER") "ESDCAN06-2BLY")
      )
      (libsource (lib "Diode") (part "TVS_array"))
    )
    (comp (ref "VD15")
      (value "~")
      (footprint "PCB_MPPT:LED: 0603B")
      (fields
        (field (name "MANUFACTURER") "Wurth")
        (field (name "VALUEMANUFACTURERPARTNUMBER") "LED, 0603, BLUE")
        (field (name "PARTNUMBER") "150060BS75000")
        (field (name "COLOR") "BLUE")
        (field (name "SHOWCOMMENT") "TX")
      )
      (libsource (lib "Diode") (part "LED_single"))
    )
    (comp (ref "VD16")
      (value "~")
      (footprint "PCB_MPPT:LED: 0603Y")
      (fields
        (field (name "MANUFACTURER") "Wurth")
        (field (name "VALUEMANUFACTURERPARTNUMBER") "LED, 0603, YELLOW")
        (field (name "PARTNUMBER") "150060YS75000")
        (field (name "COLOR") "YELLOW")
        (field (name "SHOWCOMMENT") "RX")
      )
      (libsource (lib "Diode") (part "LED_single"))
    )
    (comp (ref "VD17")
      (value "~")
      (footprint "PCB_MPPT:SOT23-6")
      (fields
        (field (name "MANUFACTURER") "ST Microelectronics")
        (field (name "VALUEMANUFACTURERPARTNUMBER") "TVS USB ESD, 5V, SOT23-6L")
        (field (name "VOLTAGE") "5V")
        (field (name "PARTNUMBER") "USBLC6-2SC6")
      )
      (libsource (lib "Diode") (part "USBLC6-2SC6"))
    )
    (comp (ref "VD18")
      (value "~")
      (footprint "PCB_MPPT:LED: 0603G")
      (fields
        (field (name "MANUFACTURER") "Wurth")
        (field (name "VALUEMANUFACTURERPARTNUMBER") "LED, 0603, GREEN")
        (field (name "PARTNUMBER") "150060VS75000")
        (field (name "COLOR") "GREEN")
        (field (name "SHOWCOMMENT") "VBUS")
      )
      (libsource (lib "Diode") (part "LED_single"))
    )
    (comp (ref "VD21")
      (value "~")
      (footprint "PCB_MPPT:DIODE: SMA")
      (fields
        (field (name "MANUFACTURER") "Vishay")
        (field (name "VALUEMANUFACTURERPARTNUMBER") "Schottky diode, 100V, 1A, , SMA")
        (field (name "VOLTAGE") "100V")
        (field (name "PARTNUMBER") "MBR0580S1-7")
      )
      (libsource (lib "Diode") (part "Schottky_single"))
    )
    (comp (ref "VD22")
      (value "~")
      (footprint "PCB_MPPT:DIODE: SMA")
      (fields
        (field (name "MANUFACTURER") "Vishay")
        (field (name "VALUEMANUFACTURERPARTNUMBER") "Schottky diode, 100V, 1A, , SMA")
        (field (name "VOLTAGE") "100V")
        (field (name "PARTNUMBER") "MBR0580S1-7")
      )
      (libsource (lib "Diode") (part "Schottky_single"))
    )
    (comp (ref "VD23")
      (value "~")
      (footprint "PCB_MPPT:LED: 0603G")
      (fields
        (field (name "MANUFACTURER") "Wurth")
        (field (name "VALUEMANUFACTURERPARTNUMBER") "LED, 0603, GREEN")
        (field (name "PARTNUMBER") "150060VS75000")
        (field (name "COLOR") "GREEN")
        (field (name "SHOWCOMMENT") "12V")
      )
      (libsource (lib "Diode") (part "LED_single"))
    )
    (comp (ref "VT9")
      (value "~")
      (footprint "PCB_MPPT:PG-TDSON-8-7")
      (description "Транзистор")
      (fields
        (field (name "MANUFACTURER") "ON Semiconductor")
        (field (name "VALUEMANUFACTURERPARTNUMBER") "MOSFET N-ch, 100V, 12A, 8-PowerTDFN")
        (field (name "PARTNUMBER") "FDMS86101")
      )
      (libsource (lib "Transistor") (part "MOSFET_N_TDSON-8"))
    )
    (comp (ref "XP7")
      (value "~")
      (footprint "PCB_MPPT:CON: IDC-20MS")
      (fields
        (field (name "MANUFACTURER") "On Shore Technology Inc.")
        (field (name "VALUEMANUFACTURERPARTNUMBER") "Connector IDC, 20pin, 2.54mm")
        (field (name "PARTNUMBER") "IDC-20M")
        (field (name "COMMENTTEXT") "\"JTAG\"")
      )
      (libsource (lib "Connector") (part "IDC-20"))
    )
    (comp (ref "XP9")
      (value "~")
      (footprint "PCB_MPPT:CON: microUSB_0475890001")
      (description "molex")
      (fields
        (field (name "MANUFACTURER") "Molex")
        (field (name "VALUEMANUFACTURERPARTNUMBER") "USB micro (AB)")
        (field (name "TYPECONNECTOR") "USB micro (AB)")
        (field (name "COMMENTTEXT") "\"USB\"")
      )
      (libsource (lib "Connector") (part "Connector_USB_micro_AB"))
    )
    (comp (ref "XS1")
      (value "~")
      (footprint "CustomCase:CON: PBD-12")
      (fields
        (field (name "MANUFACTURER") "Connfly")
        (field (name "VALUEMANUFACTURERPARTNUMBER") "Connector, 12pin, 2.54mm, 500VAC, 3A")
        (field (name "PARTNUMBER") "PBD-12")
        (field (name "COMMENTTEXT") "RESERVE")
      )
      (libsource (lib "Connector") (part "PBD-12"))
    )
    (comp (ref "XT5")
      (value "~")
      (footprint "CON: DG350-3.5-02P")
      (fields
        (field (name "MANUFACTURER") "Molex")
        (field (name "VALUEMANUFACTURERPARTNUMBER") "Terminal connector, 2pin, 3.5mm, 300VAC, 12A")
        (field (name "PARTNUMBER") "0393570002")
        (field (name "COMMENTTEXT") "\"CAN\"")
        (field (name "ROW1") "CANH")
        (field (name "ROW2") "CANL")
      )
      (libsource (lib "Connector") (part "Connector_terminal_2pin"))
    )
    (comp (ref "XT7")
      (value "~")
      (footprint "CON: DG350-3.5-02P")
      (fields
        (field (name "MANUFACTURER") "Molex")
        (field (name "VALUEMANUFACTURERPARTNUMBER") "Terminal connector, 2pin, 3.5mm, 300VAC, 12A")
        (field (name "PARTNUMBER") "0393570002")
        (field (name "COMMENTTEXT") "\"FAN 12V\"")
        (field (name "ROW1") "12V OUT")
        (field (name "ROW2") "GND")
      )
      (libsource (lib "") (part "Connector_terminal_2pin_1"))
    )
    (comp (ref "Z1")
      (value "~")
      (footprint "PCB_MPPT:OSC: ECX-53B (3.2x5)")
      (fields
        (field (name "MANUFACTURER") "ECS Inc.")
        (field (name "PARTNUMBER") "ECS-80-18-30B-AGN-TR")
        (field (name "VALUEMANUFACTURERPARTNUMBER") "Oscilator, 8MHz, 18pF, ±25ppm, case 5032")
        (field (name "FREQUENCY") "8MHz")
      )
      (libsource (lib "Oscilator") (part "Oscilator_5032"))
    )
    (comp (ref "Z2")
      (value "~")
      (footprint "CustomCase:OSC: 3215")
      (fields
        (field (name "MANUFACTURER") "NDK")
        (field (name "PARTNUMBER") "NX3215SA-32.768K-20ppm-70KOhm-7pF")
        (field (name "VALUEMANUFACTURERPARTNUMBER") "Crystal, 32.768kHz, 6pF, ±20ppm, case 3215, -40...+85°C")
        (field (name "FREQUENCY") "32.768kHz")
      )
      (libsource (lib "Oscilator") (part "Crystal_3215"))
    )
  )
  (nets
    (net (code "1") (name "/A0") (class "Default")
      (node (ref "DD1") (pin "29") (pinfunction "PA8_29") (pintype "bidirectional"))
      (node (ref "R118") (pin "2") (pinfunction "2_2") (pintype "passive"))
      (node (ref "SB4") (pin "1") (pinfunction "IN_1") (pintype "passive"))
    )
    (net (code "2") (name "/A1") (class "Default")
      (node (ref "DD1") (pin "28") (pinfunction "PB15_28") (pintype "bidirectional"))
      (node (ref "R119") (pin "2") (pinfunction "2_2") (pintype "passive"))
      (node (ref "SB4") (pin "3") (pinfunction "IN_3") (pintype "passive"))
    )
    (net (code "3") (name "/A2") (class "Default")
      (node (ref "DD1") (pin "27") (pinfunction "PB14_27") (pintype "bidirectional"))
      (node (ref "R120") (pin "2") (pinfunction "2_2") (pintype "passive"))
      (node (ref "SB4") (pin "5") (pinfunction "IN_5") (pintype "passive"))
    )
    (net (code "4") (name "/A3") (class "Default")
      (node (ref "DD1") (pin "26") (pinfunction "PB13_26") (pintype "bidirectional"))
      (node (ref "R121") (pin "2") (pinfunction "2_2") (pintype "passive"))
      (node (ref "SB4") (pin "7") (pinfunction "IN_7") (pintype "passive"))
    )
    (net (code "5") (name "/BTN1") (class "Default")
      (node (ref "C63") (pin "2") (pinfunction "2_2") (pintype "passive"))
      (node (ref "DD1") (pin "33") (pinfunction "PA12/CAN_TX_33") (pintype "bidirectional"))
      (node (ref "R94") (pin "2") (pinfunction "2_2") (pintype "passive"))
    )
    (net (code "6") (name "/CAN-RX") (class "Default")
      (node (ref "42") (pin "1") (pinfunction "1_1") (pintype "passive"))
      (node (ref "DD1") (pin "45") (pinfunction "PB8/CAN_RX_45") (pintype "bidirectional"))
      (node (ref "DD2") (pin "4") (pinfunction "RXD_4") (pintype "output"))
    )
    (net (code "7") (name "/CAN-TX") (class "Default")
      (node (ref "39") (pin "1") (pinfunction "1_1") (pintype "passive"))
      (node (ref "DD1") (pin "46") (pinfunction "PB9/CAN_TX_46") (pintype "bidirectional"))
      (node (ref "DD2") (pin "1") (pinfunction "TXD_1") (pintype "input"))
    )
    (net (code "8") (name "/CANH") (class "Default")
      (node (ref "40") (pin "1") (pinfunction "1_1") (pintype "passive"))
      (node (ref "DD2") (pin "7") (pinfunction "CANH_7") (pintype "bidirectional"))
      (node (ref "JP2") (pin "2") (pinfunction "IN_2") (pintype "passive"))
      (node (ref "VD14") (pin "1") (pintype "passive"))
      (node (ref "XT5") (pin "2") (pinfunction "2_2") (pintype "passive"))
    )
    (net (code "9") (name "/CANL") (class "Default")
      (node (ref "41") (pin "1") (pinfunction "1_1") (pintype "passive"))
      (node (ref "DD2") (pin "6") (pinfunction "CANL_6") (pintype "bidirectional"))
      (node (ref "R98") (pin "2") (pinfunction "2_2") (pintype "passive"))
      (node (ref "VD14") (pin "2") (pintype "passive"))
      (node (ref "XT5") (pin "1") (pinfunction "1_1") (pintype "passive"))
    )
    (net (code "10") (name "/D+") (class "Default")
      (node (ref "VD17") (pin "4") (pinfunction "I/O2_4") (pintype "passive"))
      (node (ref "XP9") (pin "3") (pinfunction "3_3") (pintype "passive"))
    )
    (net (code "11") (name "/D+_1") (class "Default")
      (node (ref "R107") (pin "2") (pinfunction "2_2") (pintype "passive"))
      (node (ref "VD17") (pin "3") (pinfunction "I/O2_3") (pintype "passive"))
    )
    (net (code "12") (name "/D+_2") (class "Default")
      (node (ref "DD5") (pin "3") (pinfunction "D+_3") (pintype "bidirectional"))
      (node (ref "R107") (pin "1") (pinfunction "1_1") (pintype "passive"))
    )
    (net (code "13") (name "/D-") (class "Default")
      (node (ref "VD17") (pin "6") (pinfunction "I/O1_6") (pintype "passive"))
      (node (ref "XP9") (pin "2") (pinfunction "2_2") (pintype "passive"))
    )
    (net (code "14") (name "/D-_1") (class "Default")
      (node (ref "R106") (pin "2") (pinfunction "2_2") (pintype "passive"))
      (node (ref "VD17") (pin "1") (pinfunction "I/O1_1") (pintype "passive"))
    )
    (net (code "15") (name "/D-_2") (class "Default")
      (node (ref "DD5") (pin "4") (pinfunction "D-_4") (pintype "bidirectional"))
      (node (ref "R106") (pin "1") (pinfunction "1_1") (pintype "passive"))
    )
    (net (code "16") (name "/FAN") (class "Default")
      (node (ref "DA6") (pin "2") (pinfunction "IN_2") (pintype "input"))
      (node (ref "DD1") (pin "25") (pinfunction "PB12_25") (pintype "bidirectional"))
    )
    (net (code "17") (name "/FAN_GATE") (class "Default")
      (node (ref "DA6") (pin "6") (pinfunction "OUT_6") (pintype "output"))
      (node (ref "DA6") (pin "7") (pinfunction "OUT_7") (pintype "output"))
      (node (ref "R125") (pin "2") (pinfunction "2_2") (pintype "passive"))
    )
    (net (code "18") (name "/JTCK") (class "Default")
      (node (ref "DD1") (pin "37") (pinfunction "PA14/JTCK/SWCLK_37") (pintype "bidirectional"))
      (node (ref "R70") (pin "1") (pinfunction "1_1") (pintype "passive"))
      (node (ref "R77") (pin "2") (pinfunction "2_2") (pintype "passive"))
    )
    (net (code "19") (name "/JTDI") (class "Default")
      (node (ref "DD1") (pin "38") (pinfunction "PA15/JTDI_38") (pintype "bidirectional"))
      (node (ref "R61") (pin "1") (pinfunction "1_1") (pintype "passive"))
      (node (ref "R68") (pin "1") (pinfunction "1_1") (pintype "passive"))
    )
    (net (code "20") (name "/JTDO") (class "Default")
      (node (ref "DD1") (pin "39") (pinfunction "PB3/JTDO/SWO_39") (pintype "bidirectional"))
      (node (ref "R63") (pin "1") (pinfunction "1_1") (pintype "passive"))
      (node (ref "R71") (pin "1") (pinfunction "1_1") (pintype "passive"))
    )
    (net (code "21") (name "/JTMS") (class "Default")
      (node (ref "DD1") (pin "34") (pinfunction "PA13/JTMS/SWDAT_34") (pintype "bidirectional"))
      (node (ref "R62") (pin "1") (pinfunction "1_1") (pintype "passive"))
      (node (ref "R69") (pin "1") (pinfunction "1_1") (pintype "passive"))
    )
    (net (code "22") (name "/LED1") (class "Default")
      (node (ref "DD1") (pin "14") (pinfunction "PA4_14") (pintype "bidirectional"))
      (node (ref "VD12") (pin "1") (pinfunction "A_1") (pintype "passive"))
    )
    (net (code "23") (name "/LED2") (class "Default")
      (node (ref "DD1") (pin "15") (pinfunction "PA5_15") (pintype "bidirectional"))
      (node (ref "VD13") (pin "1") (pinfunction "A_1") (pintype "passive"))
    )
    (net (code "24") (name "/NJTRST") (class "Default")
      (node (ref "DD1") (pin "40") (pinfunction "PB4/NJTRST_40") (pintype "bidirectional"))
      (node (ref "R60") (pin "1") (pinfunction "1_1") (pintype "passive"))
      (node (ref "R65") (pin "1") (pinfunction "1_1") (pintype "passive"))
    )
    (net (code "25") (name "/NRST") (class "Default")
      (node (ref "C60") (pin "2") (pinfunction "2_2") (pintype "passive"))
      (node (ref "DD1") (pin "7") (pinfunction "NRST_7") (pintype "input"))
      (node (ref "R73") (pin "1") (pinfunction "1_1") (pintype "passive"))
      (node (ref "R88") (pin "1") (pinfunction "1_1") (pintype "passive"))
      (node (ref "SB1") (pin "2") (pinfunction "2_2") (pintype "passive"))
    )
    (net (code "26") (name "/PA6") (class "Default")
      (node (ref "DD1") (pin "16") (pinfunction "PA6_16") (pintype "bidirectional"))
      (node (ref "XS1") (pin "7") (pinfunction "7_7") (pintype "power_in"))
    )
    (net (code "27") (name "/PA7") (class "Default")
      (node (ref "DD1") (pin "17") (pinfunction "PA7_17") (pintype "bidirectional"))
      (node (ref "XS1") (pin "5") (pinfunction "5_5") (pintype "power_in"))
    )
    (net (code "28") (name "/PA11") (class "Default")
      (node (ref "DD1") (pin "32") (pinfunction "PA11/CAN_RX_32") (pintype "bidirectional"))
      (node (ref "XS1") (pin "8") (pinfunction "8_8") (pintype "power_in"))
    )
    (net (code "29") (name "/PB0") (class "Default")
      (node (ref "DD1") (pin "18") (pinfunction "PB0_18") (pintype "bidirectional"))
      (node (ref "XS1") (pin "3") (pinfunction "3_3") (pintype "power_in"))
    )
    (net (code "30") (name "/PB1") (class "Default")
      (node (ref "DD1") (pin "19") (pinfunction "PB1_19") (pintype "bidirectional"))
      (node (ref "XS1") (pin "1") (pinfunction "1_1") (pintype "passive"))
    )
    (net (code "31") (name "/PB2") (class "Default")
      (node (ref "DD1") (pin "20") (pinfunction "PB2_20") (pintype "bidirectional"))
      (node (ref "XS1") (pin "2") (pinfunction "2_2") (pintype "passive"))
    )
    (net (code "32") (name "/PB10") (class "Default")
      (node (ref "DD1") (pin "21") (pinfunction "PB10_21") (pintype "bidirectional"))
      (node (ref "XS1") (pin "4") (pinfunction "4_4") (pintype "power_in"))
    )
    (net (code "33") (name "/PB11") (class "Default")
      (node (ref "DD1") (pin "22") (pinfunction "PB11_22") (pintype "bidirectional"))
      (node (ref "XS1") (pin "6") (pinfunction "6_6") (pintype "power_in"))
    )
    (net (code "34") (name "/SCL") (class "Default")
      (node (ref "DD1") (pin "42") (pinfunction "PB6/I2C1_SCL_42") (pintype "bidirectional"))
      (node (ref "DD3") (pin "1") (pinfunction "SCL_1") (pintype "input"))
      (node (ref "DD6") (pin "6") (pinfunction "SCL_6") (pintype "input"))
      (node (ref "R99") (pin "2") (pinfunction "2_2") (pintype "passive"))
    )
    (net (code "35") (name "/SDA") (class "Default")
      (node (ref "DD1") (pin "43") (pinfunction "PB7/I2C1_SDA_43") (pintype "bidirectional"))
      (node (ref "DD3") (pin "3") (pinfunction "SDA_3") (pintype "bidirectional"))
      (node (ref "DD6") (pin "5") (pinfunction "SDA_5") (pintype "bidirectional"))
      (node (ref "R100") (pin "2") (pinfunction "2_2") (pintype "passive"))
    )
    (net (code "36") (name "/TEMP") (class "Default")
      (node (ref "DD1") (pin "10") (pinfunction "PA0/ADC1_IN1_10") (pintype "bidirectional"))
    )
    (net (code "37") (name "/USART1_RX") (class "Default")
      (node (ref "DD1") (pin "31") (pinfunction "PA10/USART1_RX_31") (pintype "bidirectional"))
      (node (ref "XS1") (pin "10") (pinfunction "10_10") (pintype "power_in"))
    )
    (net (code "38") (name "/USART1_TX") (class "Default")
      (node (ref "DD1") (pin "30") (pinfunction "PA9/USART1_TX_30") (pintype "bidirectional"))
      (node (ref "XS1") (pin "12") (pinfunction "12_12") (pintype "power_in"))
    )
    (net (code "39") (name "/USART2-RX") (class "Default")
      (node (ref "47") (pin "1") (pinfunction "1_1") (pintype "passive"))
      (node (ref "DD1") (pin "13") (pinfunction "PA3/USART2_RX_13") (pintype "bidirectional"))
      (node (ref "R104") (pin "1") (pinfunction "1_1") (pintype "passive"))
      (node (ref "R114") (pin "1") (pinfunction "1_1") (pintype "passive"))
    )
    (net (code "40") (name "/USART2-TX") (class "Default")
      (node (ref "45") (pin "1") (pinfunction "1_1") (pintype "passive"))
      (node (ref "DD1") (pin "12") (pinfunction "PA2/USART2_TX_12") (pintype "bidirectional"))
      (node (ref "R103") (pin "1") (pinfunction "1_1") (pintype "passive"))
      (node (ref "R113") (pin "1") (pinfunction "1_1") (pintype "passive"))
    )
    (net (code "41") (name "3.3V") (class "Default")
      (node (ref "C51") (pin "2") (pinfunction "2_2") (pintype "passive"))
      (node (ref "C52") (pin "2") (pinfunction "2_2") (pintype "passive"))
      (node (ref "C54") (pin "2") (pinfunction "2_2") (pintype "passive"))
      (node (ref "C57") (pin "2") (pinfunction "2_2") (pintype "passive"))
      (node (ref "C64") (pin "2") (pinfunction "2_2") (pintype "passive"))
      (node (ref "C65") (pin "2") (pinfunction "2_2") (pintype "passive"))
      (node (ref "C68") (pin "1") (pinfunction "1_1") (pintype "passive"))
      (node (ref "C76") (pin "2") (pinfunction "2_2") (pintype "passive"))
      (node (ref "C77") (pin "2") (pinfunction "2_2") (pintype "passive"))
      (node (ref "DD1") (pin "24") (pinfunction "VDD_24") (pintype "passive"))
      (node (ref "DD1") (pin "36") (pinfunction "VDD_36") (pintype "passive"))
      (node (ref "DD1") (pin "48") (pinfunction "VDD_48") (pintype "passive"))
      (node (ref "DD2") (pin "3") (pinfunction "VCC_3") (pintype "passive"))
      (node (ref "DD3") (pin "4") (pinfunction "VCC_4") (pintype "power_in"))
      (node (ref "DD4") (pin "8") (pinfunction "VCC2_8") (pintype "passive"))
      (node (ref "DD6") (pin "2") (pinfunction "A1_2") (pintype "passive"))
      (node (ref "DD6") (pin "3") (pinfunction "A2_3") (pintype "passive"))
      (node (ref "DD6") (pin "8") (pinfunction "VCC_8") (pintype "power_in"))
      (node (ref "JP3") (pin "2") (pinfunction "IN_2") (pintype "passive"))
      (node (ref "L3") (pin "1") (pinfunction "1_1") (pintype "passive"))
      (node (ref "R100") (pin "1") (pinfunction "1_1") (pintype "passive"))
      (node (ref "R112") (pin "1") (pinfunction "1_1") (pintype "passive"))
      (node (ref "R113") (pin "2") (pinfunction "2_2") (pintype "passive"))
      (node (ref "R114") (pin "2") (pinfunction "2_2") (pintype "passive"))
      (node (ref "R60") (pin "2") (pinfunction "2_2") (pintype "passive"))
      (node (ref "R61") (pin "2") (pinfunction "2_2") (pintype "passive"))
      (node (ref "R62") (pin "2") (pinfunction "2_2") (pintype "passive"))
      (node (ref "R63") (pin "2") (pinfunction "2_2") (pintype "passive"))
      (node (ref "R88") (pin "2") (pinfunction "2_2") (pintype "passive"))
      (node (ref "R99") (pin "1") (pinfunction "1_1") (pintype "passive"))
      (node (ref "SB2") (pin "2") (pinfunction "2_2") (pintype "passive"))
      (node (ref "SB4") (pin "2") (pinfunction "IN_2") (pintype "passive"))
      (node (ref "SB4") (pin "4") (pinfunction "IN_4") (pintype "passive"))
      (node (ref "SB4") (pin "6") (pinfunction "IN_6") (pintype "passive"))
      (node (ref "SB4") (pin "8") (pinfunction "IN_8") (pintype "passive"))
      (node (ref "XP7") (pin "1") (pinfunction "1_1") (pintype "passive"))
      (node (ref "XP7") (pin "2") (pinfunction "2_2") (pintype "passive"))
      (node (ref "XS1") (pin "9") (pinfunction "9_9") (pintype "power_in"))
    )
    (net (code "42") (name "3.3VA") (class "Default")
      (node (ref "C55") (pin "2") (pinfunction "2_2") (pintype "passive"))
      (node (ref "C56") (pin "2") (pinfunction "2_2") (pintype "passive"))
      (node (ref "DD1") (pin "9") (pinfunction "VDDA/VREF+_9") (pintype "passive"))
      (node (ref "L3") (pin "2") (pinfunction "2_2") (pintype "passive"))
    )
    (net (code "43") (name "12V") (class "Default")
      (node (ref "C81") (pin "2") (pinfunction "2_2") (pintype "passive"))
      (node (ref "C82") (pin "2") (pinfunction "2_2") (pintype "passive"))
      (node (ref "C83") (pin "2") (pinfunction "2_2") (pintype "passive"))
      (node (ref "DA6") (pin "1") (pinfunction "VDD_1") (pintype "passive"))
      (node (ref "DA6") (pin "8") (pinfunction "VDD_8") (pintype "passive"))
      (node (ref "L4") (pin "1") (pinfunction "1_1") (pintype "passive"))
      (node (ref "R122") (pin "2") (pinfunction "2_2") (pintype "passive"))
      (node (ref "VD21") (pin "2") (pinfunction "2_2") (pintype "passive"))
      (node (ref "VD23") (pin "1") (pinfunction "A_1") (pintype "passive"))
      (node (ref "XT7") (pin "1") (pinfunction "1_1") (pintype "passive"))
    )
    (net (code "44") (name "AGND") (class "Default")
      (node (ref "B1") (pin "-") (pinfunction "-_-") (pintype "passive"))
      (node (ref "C51") (pin "1") (pinfunction "1_1") (pintype "passive"))
      (node (ref "C52") (pin "1") (pinfunction "1_1") (pintype "passive"))
      (node (ref "C53") (pin "1") (pinfunction "1_1") (pintype "passive"))
      (node (ref "C54") (pin "1") (pinfunction "1_1") (pintype "passive"))
      (node (ref "C55") (pin "1") (pinfunction "1_1") (pintype "passive"))
      (node (ref "C56") (pin "1") (pinfunction "1_1") (pintype "passive"))
      (node (ref "C57") (pin "1") (pinfunction "1_1") (pintype "passive"))
      (node (ref "C60") (pin "1") (pinfunction "1_1") (pintype "passive"))
      (node (ref "C61") (pin "1") (pinfunction "1_1") (pintype "passive"))
      (node (ref "C62") (pin "1") (pinfunction "1_1") (pintype "passive"))
      (node (ref "C63") (pin "1") (pinfunction "1_1") (pintype "passive"))
      (node (ref "C64") (pin "1") (pinfunction "1_1") (pintype "passive"))
      (node (ref "C65") (pin "1") (pinfunction "1_1") (pintype "passive"))
      (node (ref "C68") (pin "2") (pinfunction "2_2") (pintype "passive"))
      (node (ref "C74") (pin "2") (pinfunction "2_2") (pintype "passive"))
      (node (ref "C75") (pin "2") (pinfunction "2_2") (pintype "passive"))
      (node (ref "C76") (pin "1") (pinfunction "1_1") (pintype "passive"))
      (node (ref "C77") (pin "1") (pinfunction "1_1") (pintype "passive"))
      (node (ref "DA6") (pin "4") (pinfunction "AGND_4") (pintype "passive"))
      (node (ref "DD1") (pin "23") (pinfunction "VSS_23") (pintype "passive"))
      (node (ref "DD1") (pin "35") (pinfunction "VSS_35") (pintype "passive"))
      (node (ref "DD1") (pin "47") (pinfunction "VSS_47") (pintype "passive"))
      (node (ref "DD1") (pin "8") (pinfunction "VSSA/VREF-_8") (pintype "passive"))
      (node (ref "DD2") (pin "2") (pinfunction "GND_2") (pintype "passive"))
      (node (ref "DD2") (pin "8") (pinfunction "RS_8") (pintype "input"))
      (node (ref "DD3") (pin "2") (pinfunction "VSS_2") (pintype "power_in"))
      (node (ref "DD3") (pin "5") (pinfunction "WP_5") (pintype "input"))
      (node (ref "DD4") (pin "5") (pinfunction "GND2_5") (pintype "passive"))
      (node (ref "DD6") (pin "4") (pinfunction "GND_4") (pintype "power_in"))
      (node (ref "DD6") (pin "7") (pinfunction "WP_7") (pintype "passive"))
      (node (ref "NT2") (pin "1") (pinfunction "1_1") (pintype "passive"))
      (node (ref "R115") (pin "1") (pinfunction "1_1") (pintype "passive"))
      (node (ref "R116") (pin "1") (pinfunction "1_1") (pintype "passive"))
      (node (ref "R117") (pin "1") (pinfunction "1_1") (pintype "passive"))
      (node (ref "R118") (pin "1") (pinfunction "1_1") (pintype "passive"))
      (node (ref "R119") (pin "1") (pinfunction "1_1") (pintype "passive"))
      (node (ref "R120") (pin "1") (pinfunction "1_1") (pintype "passive"))
      (node (ref "R121") (pin "1") (pinfunction "1_1") (pintype "passive"))
      (node (ref "R77") (pin "1") (pinfunction "1_1") (pintype "passive"))
      (node (ref "R92") (pin "1") (pinfunction "1_1") (pintype "passive"))
      (node (ref "R95") (pin "1") (pinfunction "1_1") (pintype "passive"))
      (node (ref "R96") (pin "1") (pinfunction "1_1") (pintype "passive"))
      (node (ref "R97") (pin "1") (pinfunction "1_1") (pintype "passive"))
      (node (ref "SB1") (pin "1") (pinfunction "1_1") (pintype "passive"))
      (node (ref "VD14") (pin "3") (pintype "passive"))
      (node (ref "XP7") (pin "10") (pinfunction "10_10") (pintype "power_in"))
      (node (ref "XP7") (pin "12") (pinfunction "12_12") (pintype "power_in"))
      (node (ref "XP7") (pin "14") (pinfunction "14_14") (pintype "power_in"))
      (node (ref "XP7") (pin "16") (pinfunction "16_16") (pintype "power_in"))
      (node (ref "XP7") (pin "18") (pinfunction "18_18") (pintype "power_in"))
      (node (ref "XP7") (pin "20") (pinfunction "20_20") (pintype "power_in"))
      (node (ref "XP7") (pin "4") (pinfunction "4_4") (pintype "power_in"))
      (node (ref "XP7") (pin "6") (pinfunction "6_6") (pintype "power_in"))
      (node (ref "XP7") (pin "8") (pinfunction "8_8") (pintype "power_in"))
      (node (ref "XS1") (pin "11") (pinfunction "11_11") (pintype "power_in"))
      (node (ref "Z1") (pin "2") (pinfunction "2_2") (pintype "passive"))
      (node (ref "Z1") (pin "4") (pinfunction "4_4") (pintype "passive"))
    )
    (net (code "45") (name "GND") (class "Default")
      (node (ref "C78") (pin "1") (pinfunction "1_1") (pintype "passive"))
      (node (ref "C79") (pin "1") (pinfunction "1_1") (pintype "passive"))
      (node (ref "C81") (pin "1") (pinfunction "1_1") (pintype "passive"))
      (node (ref "C82") (pin "1") (pinfunction "1_1") (pintype "passive"))
      (node (ref "C83") (pin "1") (pinfunction "1_1") (pintype "passive"))
      (node (ref "DA5") (pin "2") (pinfunction "GND_2") (pintype "power_in"))
      (node (ref "DA6") (pin "5") (pinfunction "PGND_5") (pintype "passive"))
      (node (ref "NT2") (pin "2") (pinfunction "2_2") (pintype "passive"))
      (node (ref "R123") (pin "2") (pinfunction "2_2") (pintype "passive"))
      (node (ref "R124") (pin "1") (pinfunction "1_1") (pintype "passive"))
      (node (ref "R126") (pin "2") (pinfunction "2_2") (pintype "passive"))
      (node (ref "VD22") (pin "1") (pinfunction "1_1") (pintype "passive"))
      (node (ref "VT9") (pin "1") (pinfunction "S_1") (pintype "passive"))
      (node (ref "VT9") (pin "2") (pinfunction "S_2") (pintype "passive"))
      (node (ref "VT9") (pin "3") (pinfunction "S_3") (pintype "passive"))
    )
    (net (code "46") (name "GND_USB") (class "Default")
      (node (ref "50") (pin "1") (pinfunction "1_1") (pintype "passive"))
      (node (ref "C66") (pin "2") (pinfunction "2_2") (pintype "passive"))
      (node (ref "C67") (pin "1") (pinfunction "1_1") (pintype "passive"))
      (node (ref "C69") (pin "2") (pinfunction "2_2") (pintype "passive"))
      (node (ref "C70") (pin "2") (pinfunction "2_2") (pintype "passive"))
      (node (ref "C71") (pin "2") (pinfunction "2_2") (pintype "passive"))
      (node (ref "C72") (pin "1") (pinfunction "1_1") (pintype "passive"))
      (node (ref "DD4") (pin "4") (pinfunction "GND1_4") (pintype "passive"))
      (node (ref "DD5") (pin "0") (pinfunction "PAD_0") (pintype "passive"))
      (node (ref "DD5") (pin "2") (pinfunction "GND_2") (pintype "passive"))
      (node (ref "R109") (pin "1") (pinfunction "1_1") (pintype "passive"))
      (node (ref "R110") (pin "2") (pinfunction "2_2") (pintype "passive"))
      (node (ref "VD17") (pin "2") (pinfunction "GND_2") (pintype "passive"))
      (node (ref "VD18") (pin "2") (pinfunction "C_2") (pintype "passive"))
      (node (ref "XP9") (pin "0") (pinfunction "0_0") (pintype "passive"))
      (node (ref "XP9") (pin "5") (pinfunction "5_5") (pintype "passive"))
    )
    (net (code "47") (name "Net-(C62-Pad2)") (class "Default")
      (node (ref "C62") (pin "2") (pinfunction "2_2") (pintype "passive"))
      (node (ref "R89") (pin "2") (pinfunction "2_2") (pintype "passive"))
      (node (ref "Z1") (pin "3") (pinfunction "3_3") (pintype "passive"))
    )
    (net (code "48") (name "Net-(DA5-CB)") (class "Default")
      (node (ref "C80") (pin "2") (pinfunction "2_2") (pintype "passive"))
      (node (ref "DA5") (pin "1") (pinfunction "CB_1") (pintype "power_in"))
    )
    (net (code "49") (name "Net-(DA5-FB)") (class "Default")
      (node (ref "DA5") (pin "3") (pinfunction "FB_3") (pintype "power_in"))
      (node (ref "R122") (pin "1") (pinfunction "1_1") (pintype "passive"))
      (node (ref "R123") (pin "1") (pinfunction "1_1") (pintype "passive"))
    )
    (net (code "50") (name "Net-(DA5-SW)") (class "Default")
      (node (ref "C80") (pin "1") (pinfunction "1_1") (pintype "passive"))
      (node (ref "DA5") (pin "6") (pinfunction "SW_6") (pintype "power_in"))
      (node (ref "L4") (pin "2") (pinfunction "2_2") (pintype "passive"))
      (node (ref "VD22") (pin "2") (pinfunction "2_2") (pintype "passive"))
    )
    (net (code "51") (name "Net-(DD1-BOOT0)") (class "Default")
      (node (ref "DD1") (pin "44") (pinfunction "BOOT0_44") (pintype "input"))
      (node (ref "JP3") (pin "1") (pinfunction "IN_1") (pintype "passive"))
      (node (ref "R92") (pin "2") (pinfunction "2_2") (pintype "passive"))
    )
    (net (code "52") (name "Net-(DD1-OSC-IN)") (class "Default")
      (node (ref "C61") (pin "2") (pinfunction "2_2") (pintype "passive"))
      (node (ref "DD1") (pin "5") (pinfunction "OSC-IN_5") (pintype "bidirectional"))
      (node (ref "Z1") (pin "1") (pinfunction "1_1") (pintype "passive"))
    )
    (net (code "53") (name "Net-(DD1-OSC-OUT)") (class "Default")
      (node (ref "DD1") (pin "6") (pinfunction "OSC-OUT_6") (pintype "bidirectional"))
      (node (ref "R89") (pin "1") (pinfunction "1_1") (pintype "passive"))
    )
    (net (code "54") (name "Net-(DD1-PC14{slash}OSC32_IN)") (class "Default")
      (node (ref "C74") (pin "1") (pinfunction "1_1") (pintype "passive"))
      (node (ref "DD1") (pin "3") (pinfunction "PC14/OSC32_IN_3") (pintype "bidirectional"))
      (node (ref "Z2") (pin "2") (pinfunction "2_2") (pintype "passive"))
    )
    (net (code "55") (name "Net-(DD1-PC15{slash}OSC32_OUT)") (class "Default")
      (node (ref "C75") (pin "1") (pinfunction "1_1") (pintype "passive"))
      (node (ref "DD1") (pin "4") (pinfunction "PC15/OSC32_OUT_4") (pintype "bidirectional"))
      (node (ref "Z2") (pin "1") (pinfunction "1_1") (pintype "passive"))
    )
    (net (code "56") (name "Net-(DD1-VBAT)") (class "Default")
      (node (ref "B1") (pin "+") (pinfunction "+_+") (pintype "passive"))
      (node (ref "C53") (pin "2") (pinfunction "2_2") (pintype "passive"))
      (node (ref "DD1") (pin "1") (pinfunction "VBAT_1") (pintype "passive"))
      (node (ref "R112") (pin "2") (pinfunction "2_2") (pintype "passive"))
    )
    (net (code "57") (name "Net-(DD4-INA)") (class "Default")
      (node (ref "DD4") (pin "7") (pinfunction "INA_7") (pintype "input"))
      (node (ref "R103") (pin "2") (pinfunction "2_2") (pintype "passive"))
    )
    (net (code "58") (name "Net-(DD4-INB)") (class "Default")
      (node (ref "DD4") (pin "3") (pinfunction "INB_3") (pintype "input"))
      (node (ref "DD5") (pin "21") (pinfunction "TXD_21") (pintype "output"))
      (node (ref "VD15") (pin "2") (pinfunction "C_2") (pintype "passive"))
    )
    (net (code "59") (name "Net-(DD4-OUTA)") (class "Default")
      (node (ref "DD4") (pin "2") (pinfunction "OUTA_2") (pintype "output"))
      (node (ref "DD5") (pin "20") (pinfunction "RXD_20") (pintype "input"))
      (node (ref "VD16") (pin "2") (pinfunction "C_2") (pintype "passive"))
    )
    (net (code "60") (name "Net-(DD4-OUTB)") (class "Default")
      (node (ref "DD4") (pin "6") (pinfunction "OUTB_6") (pintype "output"))
      (node (ref "R104") (pin "2") (pinfunction "2_2") (pintype "passive"))
    )
    (net (code "61") (name "Net-(DD5-SUSPENDb)") (class "Default")
      (node (ref "49") (pin "1") (pinfunction "1_1") (pintype "passive"))
      (node (ref "DD5") (pin "15") (pinfunction "SUSPENDb_15") (pintype "output"))
      (node (ref "R109") (pin "2") (pinfunction "2_2") (pintype "passive"))
    )
    (net (code "62") (name "Net-(DD5-VBUS)") (class "Default")
      (node (ref "DD5") (pin "8") (pinfunction "VBUS_8") (pintype "passive"))
      (node (ref "R110") (pin "1") (pinfunction "1_1") (pintype "passive"))
      (node (ref "R111") (pin "1") (pinfunction "1_1") (pintype "passive"))
    )
    (net (code "63") (name "Net-(DD5-~{RSTb})") (class "Default")
      (node (ref "DD5") (pin "9") (pinfunction "~{RSTb}_9") (pintype "input"))
      (node (ref "R108") (pin "2") (pinfunction "2_2") (pintype "passive"))
    )
    (net (code "64") (name "Net-(JP2-IN-Pad1)") (class "Default")
      (node (ref "JP2") (pin "1") (pinfunction "IN_1") (pintype "passive"))
      (node (ref "R98") (pin "1") (pinfunction "1_1") (pintype "passive"))
    )
    (net (code "65") (name "Net-(R65-Pad2)") (class "Default")
      (node (ref "R65") (pin "2") (pinfunction "2_2") (pintype "passive"))
      (node (ref "XP7") (pin "3") (pinfunction "3_3") (pintype "power_in"))
    )
    (net (code "66") (name "Net-(R68-Pad2)") (class "Default")
      (node (ref "R68") (pin "2") (pinfunction "2_2") (pintype "passive"))
      (node (ref "XP7") (pin "5") (pinfunction "5_5") (pintype "power_in"))
    )
    (net (code "67") (name "Net-(R69-Pad2)") (class "Default")
      (node (ref "R69") (pin "2") (pinfunction "2_2") (pintype "passive"))
      (node (ref "XP7") (pin "7") (pinfunction "7_7") (pintype "power_in"))
    )
    (net (code "68") (name "Net-(R70-Pad2)") (class "Default")
      (node (ref "R70") (pin "2") (pinfunction "2_2") (pintype "passive"))
      (node (ref "XP7") (pin "9") (pinfunction "9_9") (pintype "power_in"))
    )
    (net (code "69") (name "Net-(R71-Pad2)") (class "Default")
      (node (ref "R71") (pin "2") (pinfunction "2_2") (pintype "passive"))
      (node (ref "XP7") (pin "13") (pinfunction "13_13") (pintype "power_in"))
    )
    (net (code "70") (name "Net-(R73-Pad2)") (class "Default")
      (node (ref "R73") (pin "2") (pinfunction "2_2") (pintype "passive"))
      (node (ref "XP7") (pin "15") (pinfunction "15_15") (pintype "power_in"))
    )
    (net (code "71") (name "Net-(R94-Pad1)") (class "Default")
      (node (ref "R94") (pin "1") (pinfunction "1_1") (pintype "passive"))
      (node (ref "R97") (pin "2") (pinfunction "2_2") (pintype "passive"))
      (node (ref "SB2") (pin "1") (pinfunction "1_1") (pintype "passive"))
    )
    (net (code "72") (name "Net-(R115-Pad2)") (class "Default")
      (node (ref "R115") (pin "2") (pinfunction "2_2") (pintype "passive"))
      (node (ref "XP7") (pin "19") (pinfunction "19_19") (pintype "power_in"))
    )
    (net (code "73") (name "Net-(R116-Pad2)") (class "Default")
      (node (ref "R116") (pin "2") (pinfunction "2_2") (pintype "passive"))
      (node (ref "XP7") (pin "17") (pinfunction "17_17") (pintype "power_in"))
    )
    (net (code "74") (name "Net-(R117-Pad2)") (class "Default")
      (node (ref "R117") (pin "2") (pinfunction "2_2") (pintype "passive"))
      (node (ref "XP7") (pin "11") (pinfunction "11_11") (pintype "power_in"))
    )
    (net (code "75") (name "Net-(VD12-C)") (class "Default")
      (node (ref "R95") (pin "2") (pinfunction "2_2") (pintype "passive"))
      (node (ref "VD12") (pin "2") (pinfunction "C_2") (pintype "passive"))
    )
    (net (code "76") (name "Net-(VD13-C)") (class "Default")
      (node (ref "R96") (pin "2") (pinfunction "2_2") (pintype "passive"))
      (node (ref "VD13") (pin "2") (pinfunction "C_2") (pintype "passive"))
    )
    (net (code "77") (name "Net-(VD15-A)") (class "Default")
      (node (ref "R101") (pin "2") (pinfunction "2_2") (pintype "passive"))
      (node (ref "VD15") (pin "1") (pinfunction "A_1") (pintype "passive"))
    )
    (net (code "78") (name "Net-(VD16-A)") (class "Default")
      (node (ref "R102") (pin "2") (pinfunction "2_2") (pintype "passive"))
      (node (ref "VD16") (pin "1") (pinfunction "A_1") (pintype "passive"))
    )
    (net (code "79") (name "Net-(VD18-A)") (class "Default")
      (node (ref "R105") (pin "2") (pinfunction "2_2") (pintype "passive"))
      (node (ref "VD18") (pin "1") (pinfunction "A_1") (pintype "passive"))
    )
    (net (code "80") (name "Net-(VD21-Pad1)") (class "Default")
      (node (ref "VD21") (pin "1") (pinfunction "1_1") (pintype "passive"))
      (node (ref "VT9") (pin "5") (pinfunction "D_5") (pintype "passive"))
      (node (ref "VT9") (pin "6") (pinfunction "D_6") (pintype "passive"))
      (node (ref "VT9") (pin "7") (pinfunction "D_7") (pintype "passive"))
      (node (ref "VT9") (pin "8") (pinfunction "D_8") (pintype "passive"))
      (node (ref "XT7") (pin "2") (pinfunction "2_2") (pintype "passive"))
    )
    (net (code "81") (name "Net-(VD23-C)") (class "Default")
      (node (ref "R124") (pin "2") (pinfunction "2_2") (pintype "passive"))
      (node (ref "VD23") (pin "2") (pinfunction "C_2") (pintype "passive"))
    )
    (net (code "82") (name "Net-(VT9-G)") (class "Default")
      (node (ref "R125") (pin "1") (pinfunction "1_1") (pintype "passive"))
      (node (ref "R126") (pin "1") (pinfunction "1_1") (pintype "passive"))
      (node (ref "VT9") (pin "4") (pinfunction "G_4") (pintype "passive"))
    )
    (net (code "83") (name "VBAT") (class "Default")
      (node (ref "C78") (pin "2") (pinfunction "2_2") (pintype "passive"))
      (node (ref "C79") (pin "2") (pinfunction "2_2") (pintype "passive"))
      (node (ref "DA5") (pin "5") (pinfunction "VIN_5") (pintype "power_in"))
    )
    (net (code "84") (name "VCC5V-USB") (class "Default")
      (node (ref "44") (pin "1") (pinfunction "1_1") (pintype "passive"))
      (node (ref "C66") (pin "1") (pinfunction "1_1") (pintype "passive"))
      (node (ref "C67") (pin "2") (pinfunction "2_2") (pintype "passive"))
      (node (ref "C70") (pin "1") (pinfunction "1_1") (pintype "passive"))
      (node (ref "DD5") (pin "7") (pinfunction "VREGIN_7") (pintype "passive"))
      (node (ref "R105") (pin "1") (pinfunction "1_1") (pintype "passive"))
      (node (ref "R111") (pin "2") (pinfunction "2_2") (pintype "passive"))
      (node (ref "VD17") (pin "5") (pinfunction "VBUS_5") (pintype "passive"))
      (node (ref "XP9") (pin "1") (pinfunction "1_1") (pintype "passive"))
    )
    (net (code "85") (name "VDD1") (class "Default")
      (node (ref "48") (pin "1") (pinfunction "1_1") (pintype "passive"))
      (node (ref "C69") (pin "1") (pinfunction "1_1") (pintype "passive"))
      (node (ref "C71") (pin "1") (pinfunction "1_1") (pintype "passive"))
      (node (ref "C72") (pin "2") (pinfunction "2_2") (pintype "passive"))
      (node (ref "DD4") (pin "1") (pinfunction "VCC1_1") (pintype "passive"))
      (node (ref "DD5") (pin "5") (pinfunction "VIO_5") (pintype "passive"))
      (node (ref "DD5") (pin "6") (pinfunction "VDD_6") (pintype "passive"))
      (node (ref "R101") (pin "1") (pinfunction "1_1") (pintype "passive"))
      (node (ref "R102") (pin "1") (pinfunction "1_1") (pintype "passive"))
      (node (ref "R108") (pin "1") (pinfunction "1_1") (pintype "passive"))
    )
    (net (code "86") (name "unconnected-(DA5-SHDN-Pad4)") (class "Default")
      (node (ref "DA5") (pin "4") (pinfunction "SHDN_4") (pintype "power_in+no_connect"))
    )
    (net (code "87") (name "unconnected-(DA6-EN-Pad3)") (class "Default")
      (node (ref "DA6") (pin "3") (pinfunction "EN_3") (pintype "input+no_connect"))
    )
    (net (code "88") (name "unconnected-(DD1-PA1{slash}ADC1_IN2-Pad11)") (class "Default")
      (node (ref "DD1") (pin "11") (pinfunction "PA1/ADC1_IN2_11") (pintype "bidirectional+no_connect"))
    )
    (net (code "89") (name "unconnected-(DD1-PB5-Pad41)") (class "Default")
      (node (ref "DD1") (pin "41") (pinfunction "PB5_41") (pintype "bidirectional+no_connect"))
    )
    (net (code "90") (name "unconnected-(DD1-PC13-Pad2)") (class "Default")
      (node (ref "DD1") (pin "2") (pinfunction "PC13_2") (pintype "bidirectional+no_connect"))
    )
    (net (code "91") (name "unconnected-(DD2-VREF-Pad5)") (class "Default")
      (node (ref "DD2") (pin "5") (pinfunction "VREF_5") (pintype "passive+no_connect"))
    )
    (net (code "92") (name "unconnected-(DD5-CTS-Pad18)") (class "Default")
      (node (ref "DD5") (pin "18") (pinfunction "CTS_18") (pintype "input+no_connect"))
    )
    (net (code "93") (name "unconnected-(DD5-DSR-Pad22)") (class "Default")
      (node (ref "DD5") (pin "22") (pinfunction "DSR_22") (pintype "input+no_connect"))
    )
    (net (code "94") (name "unconnected-(DD5-DTR-Pad23)") (class "Default")
      (node (ref "DD5") (pin "23") (pinfunction "DTR_23") (pintype "output+no_connect"))
    )
    (net (code "95") (name "unconnected-(DD5-RI{slash}CLK-Pad1)") (class "Default")
      (node (ref "DD5") (pin "1") (pinfunction "RI/CLK_1") (pintype "bidirectional+no_connect"))
    )
    (net (code "96") (name "unconnected-(DD5-RTS-Pad19)") (class "Default")
      (node (ref "DD5") (pin "19") (pinfunction "RTS_19") (pintype "output+no_connect"))
    )
    (net (code "97") (name "unconnected-(DD5-SUSPEND-Pad17)") (class "Default")
      (node (ref "DD5") (pin "17") (pinfunction "SUSPEND_17") (pintype "output+no_connect"))
    )
    (net (code "98") (name "unconnected-(XP9-Pad4)") (class "Default")
      (node (ref "XP9") (pin "4") (pinfunction "4_4") (pintype "passive+no_connect"))
    )
  )
)
